# 94330_SKYPULSE_IOC_V1_3.net
KiCad netlist of a schematic drawn in Altium Designer
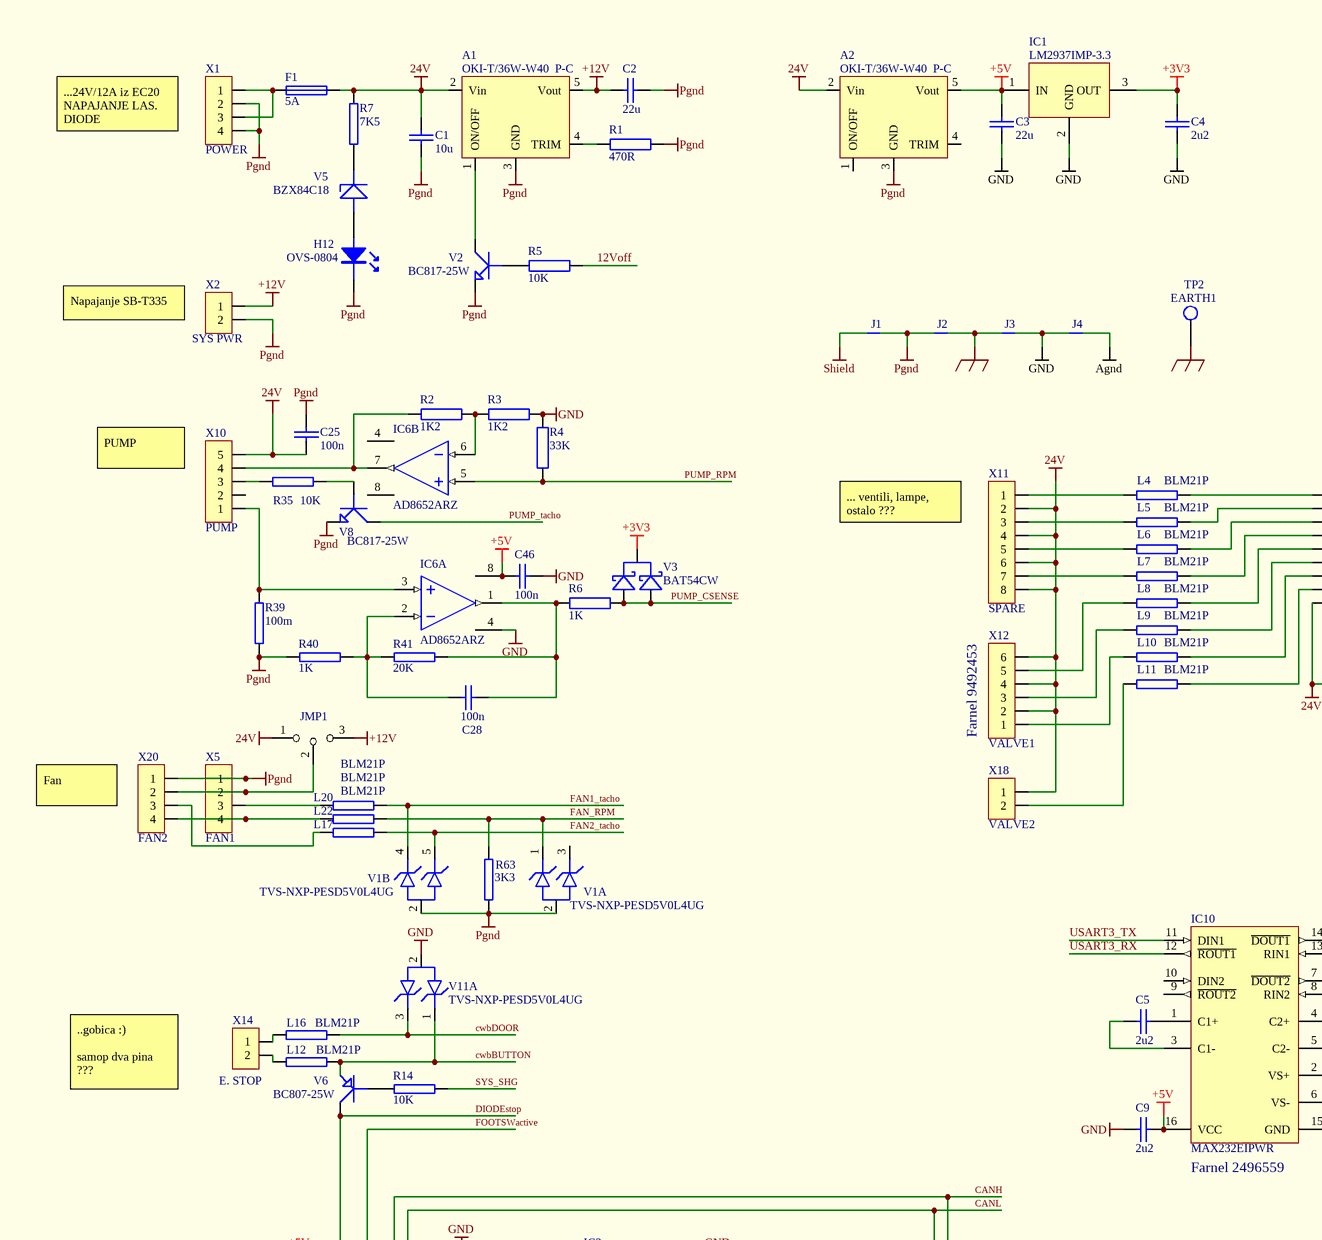
[diagram p0: 94330_SKYPULSE IOC_V1.3.SchDoc, top left]
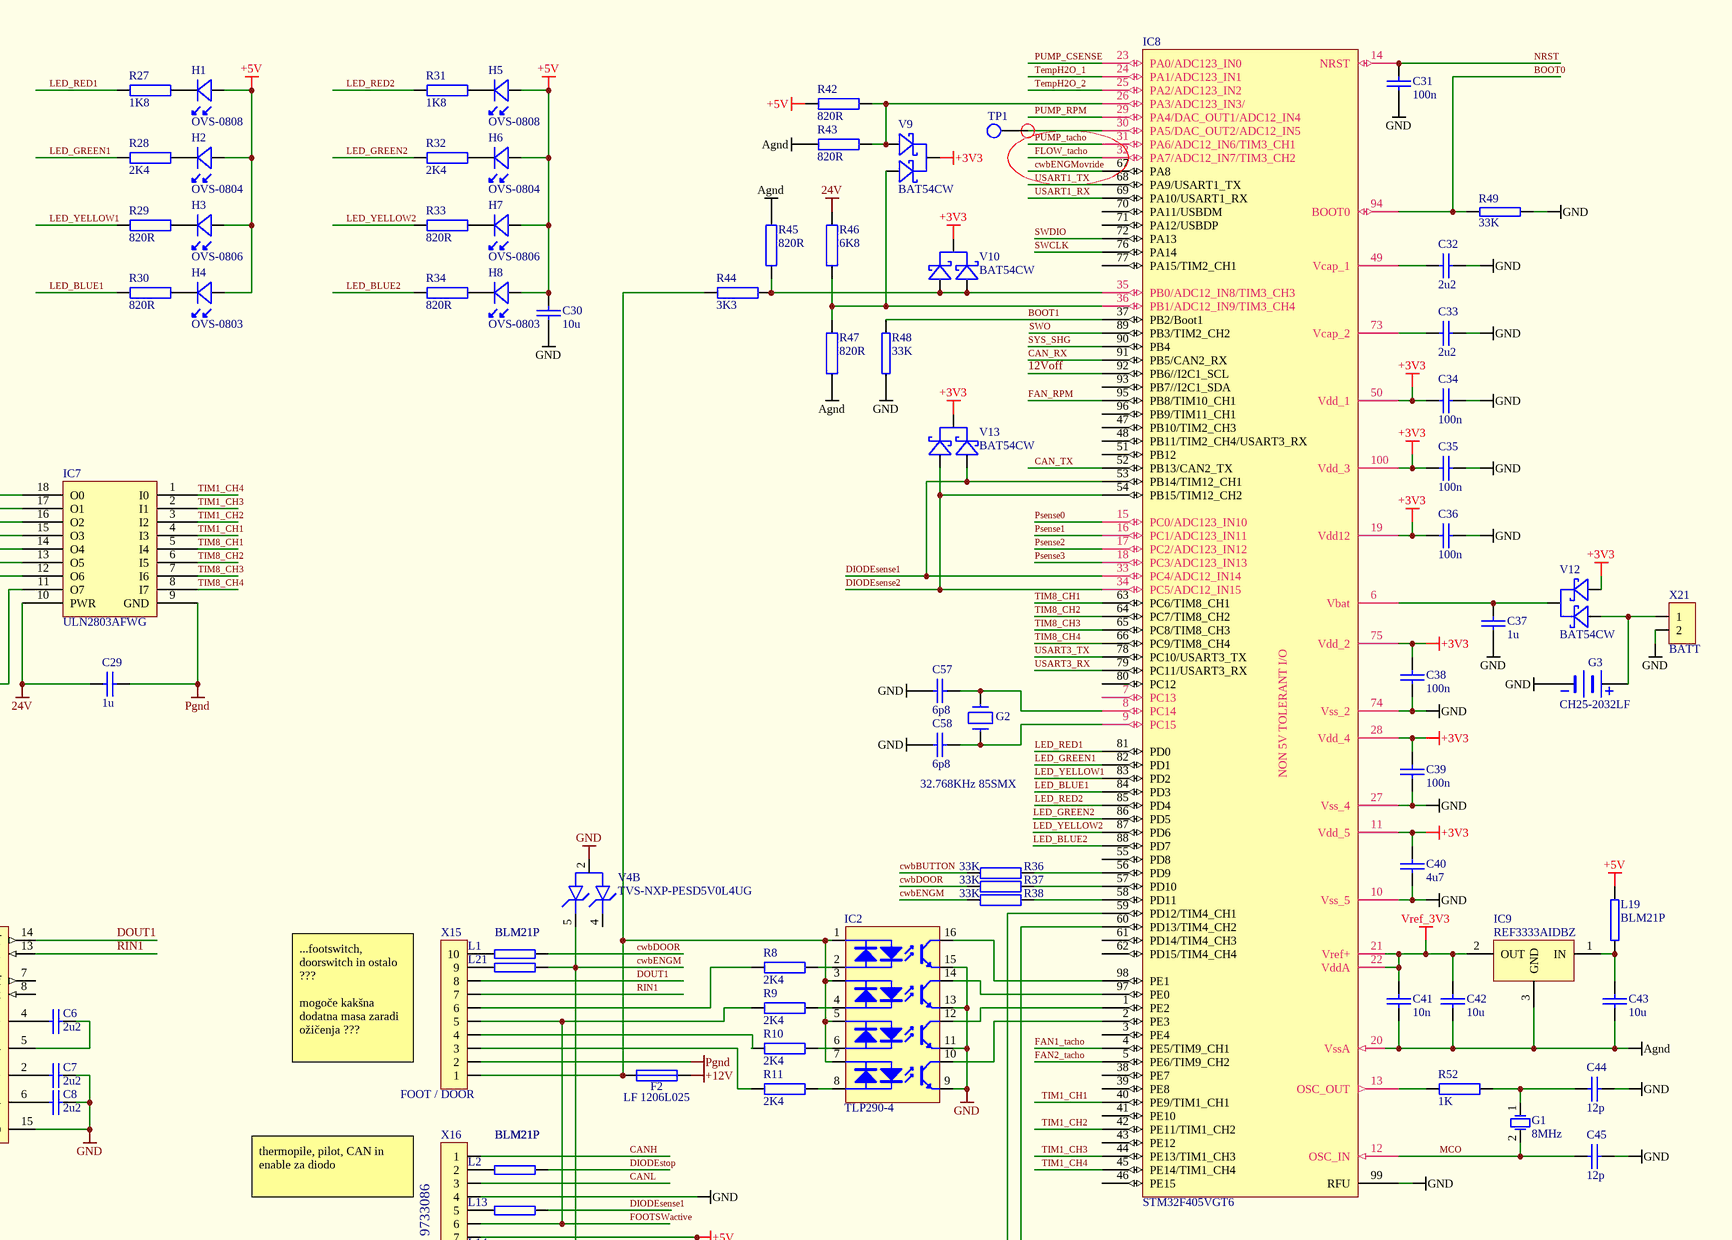
[diagram p1: 94330_SKYPULSE IOC_V1.3.SchDoc, top right]
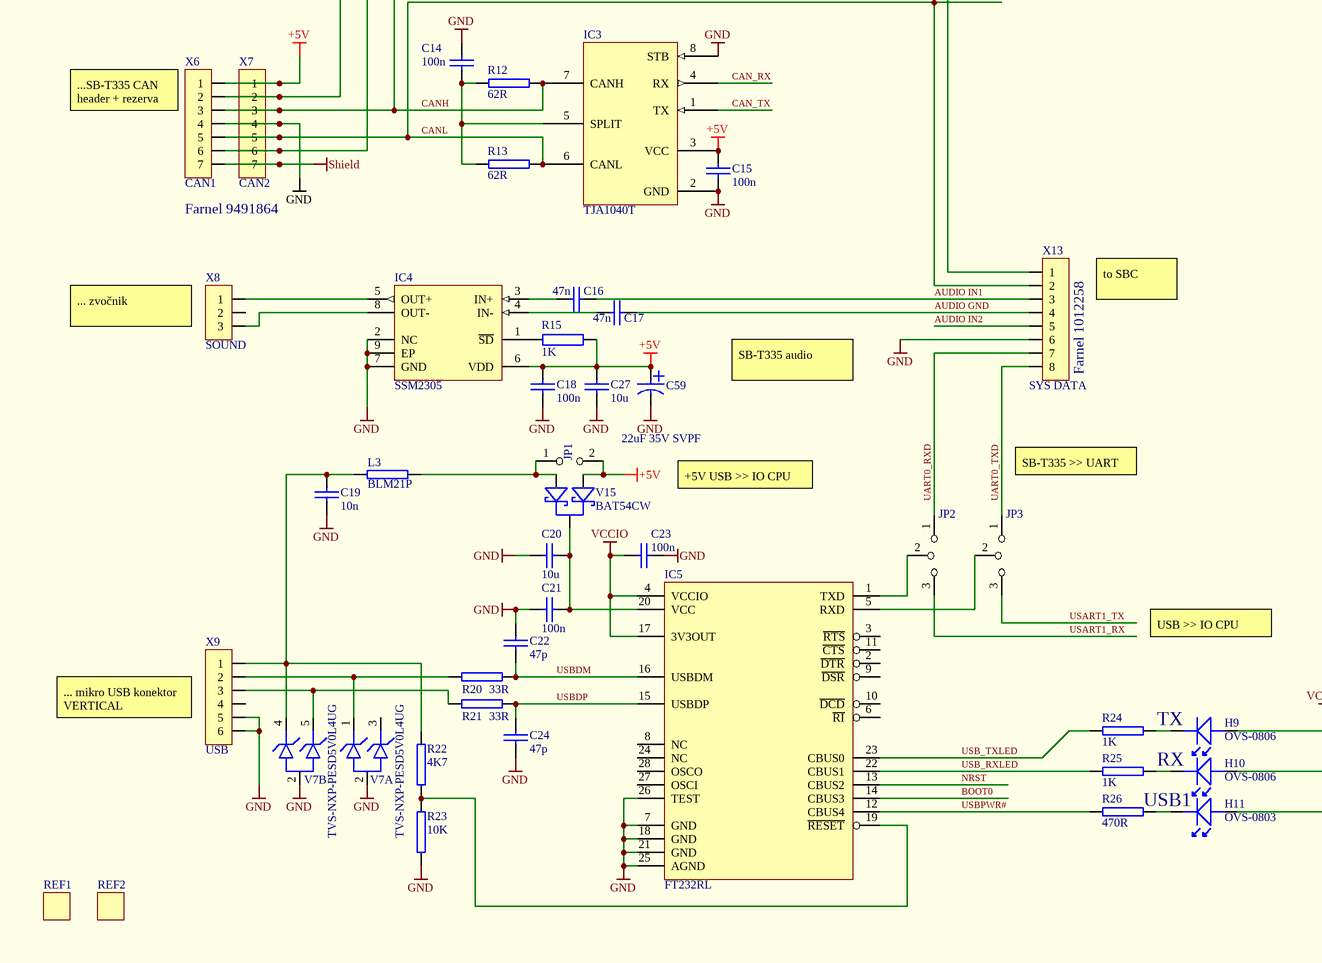
[diagram p2: 94330_SKYPULSE IOC_V1.3.SchDoc, bottom left]
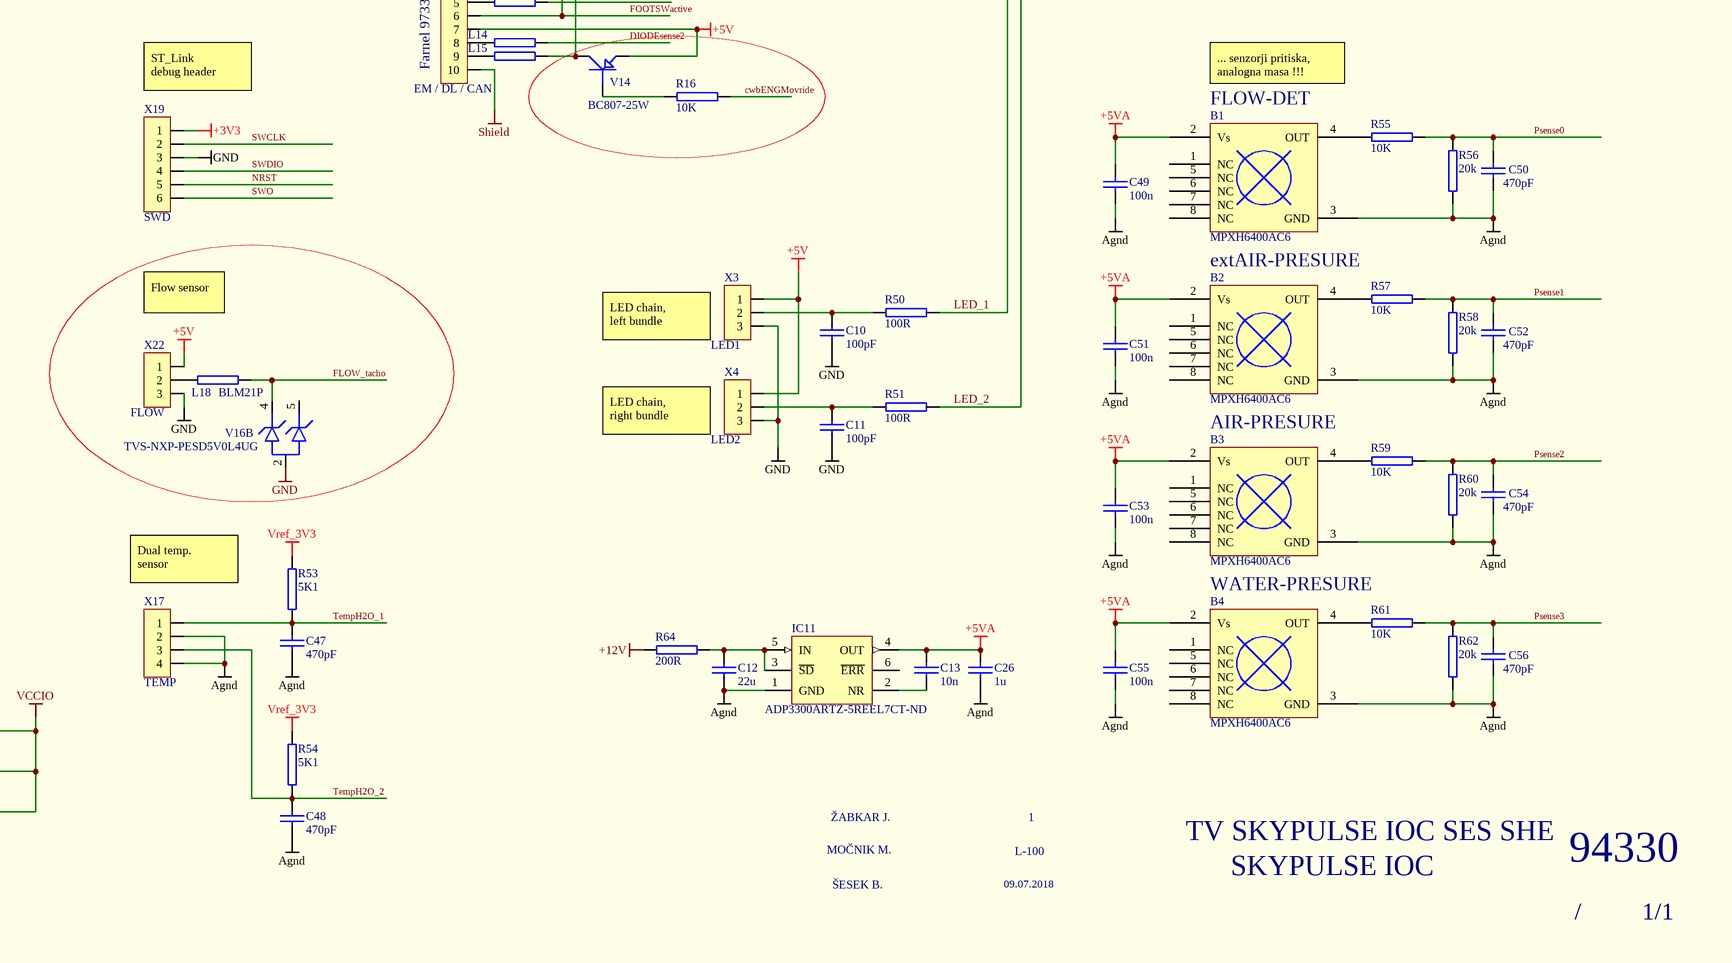
[diagram p3: 94330_SKYPULSE IOC_V1.3.SchDoc, bottom right]

(export (version "E")
  (design (tool "Eeschema 10.0.6"))
  (components
    (comp (ref "A1")
      (value "OKI-T/36W-W40  P-C")
      (footprint "DC-DC_OKI-T/36W-W40")
      (description "Selectable Output DC-DC Converter")
      (libsource (lib "Mlk-sch") (part "MURATA_OKI-T/36W-W40  X-C"))
    )
    (comp (ref "A2")
      (value "OKI-T/36W-W40  P-C")
      (footprint "DC-DC_OKI-T/36W-W40")
      (description "Selectable Output DC-DC Converter")
      (libsource (lib "Mlk-sch") (part "MURATA_OKI-T/36W-W40  X-C"))
    )
    (comp (ref "B1")
      (value "MPXH6400AC6")
      (footprint "SOIC127P1030-8N_MPXH6400AC6")
      (description "Pressure sensor, 400kPa")
      (libsource (lib "*") (part "MPXH6400A"))
    )
    (comp (ref "B2")
      (value "MPXH6400AC6")
      (footprint "SOIC127P1030-8N_MPXH6400AC6")
      (description "Pressure sensor, 400kPa")
      (libsource (lib "*") (part "MPXH6400A"))
    )
    (comp (ref "B3")
      (value "MPXH6400AC6")
      (footprint "SOIC127P1030-8N_MPXH6400AC6")
      (description "Pressure sensor, 400kPa")
      (libsource (lib "*") (part "MPXH6400A"))
    )
    (comp (ref "B4")
      (value "MPXH6400AC6")
      (footprint "SOIC127P1030-8N_MPXH6400AC6")
      (description "Pressure sensor, 400kPa")
      (libsource (lib "*") (part "MPXH6400A"))
    )
    (comp (ref "C1")
      (value "10u")
      (footprint "CAPC3225N")
      (description "KOND. 1210 10uF 50V 20% X5S")
      (libsource (lib "altium-import") (part "root_2_Cap_"))
    )
    (comp (ref "C2")
      (value "22u")
      (footprint "CAPC3225N")
      (description "KOND. 1210 22uF 25V 10% X5R")
      (libsource (lib "altium-import") (part "root_1_Cap_"))
    )
    (comp (ref "C3")
      (value "22u")
      (footprint "CAPC3225N")
      (description "KOND. 1210 22uF 25V 10% X5R")
      (libsource (lib "altium-import") (part "root_0_Cap_"))
    )
    (comp (ref "C4")
      (value "2u2")
      (footprint "0805-C-IPC-V")
      (description "KOND. 0805 2,2uF 25V 10% X7R")
      (libsource (lib "altium-import") (part "root_0_Cap_"))
    )
    (comp (ref "C5")
      (value "2u2")
      (footprint "0805-C-IPC-V")
      (description "KOND. 0805 2,2uF 25V 10% X7R")
      (libsource (lib "altium-import") (part "root_1_Cap_"))
    )
    (comp (ref "C6")
      (value "2u2")
      (footprint "0805-C-IPC-V")
      (description "KOND. 0805 2,2uF 25V 10% X7R")
      (libsource (lib "altium-import") (part "root_1_Cap_"))
    )
    (comp (ref "C7")
      (value "2u2")
      (footprint "0805-C-IPC-V")
      (description "KOND. 0805 2,2uF 25V 10% X7R")
      (libsource (lib "altium-import") (part "root_1_Cap_"))
    )
    (comp (ref "C8")
      (value "2u2")
      (footprint "0805-C-IPC-V")
      (description "KOND. 0805 2,2uF 25V 10% X7R")
      (libsource (lib "altium-import") (part "root_1_Cap_"))
    )
    (comp (ref "C9")
      (value "2u2")
      (footprint "0805-C-IPC-V")
      (description "KOND. 0805 2,2uF 25V 10% X7R")
      (libsource (lib "altium-import") (part "root_3_Cap_"))
    )
    (comp (ref "C10")
      (value "100pF")
      (footprint "0805-C-IPC-V")
      (description "KOND. 0805 100pF 50V 5% COG")
      (libsource (lib "*") (part "C"))
    )
    (comp (ref "C11")
      (value "100pF")
      (footprint "0805-C-IPC-V")
      (description "KOND. 0805 100pF 50V 5% COG")
      (libsource (lib "*") (part "C"))
    )
    (comp (ref "C12")
      (value "22u")
      (footprint "CAPC3225N")
      (description "KOND. 1210 22uF 25V 10% X5R")
      (libsource (lib "altium-import") (part "root_2_Cap_"))
    )
    (comp (ref "C13")
      (value "10n")
      (footprint "0805-C-IPC-V")
      (description "KOND. 0805 10nF 10% 50V X7R")
      (libsource (lib "Main") (part "C"))
    )
    (comp (ref "C14")
      (value "100n")
      (footprint "0805-C-IPC-V")
      (description "KOND. 0805 100nF 50V 10% X7R")
      (libsource (lib "Main") (part "C"))
    )
    (comp (ref "C15")
      (value "100n")
      (footprint "0805-C-IPC-V")
      (description "KOND. 0805 100nF 50V 10% X7R")
      (libsource (lib "Main") (part "C"))
    )
    (comp (ref "C16")
      (value "47n")
      (footprint "0805-C-IPC-V")
      (description "KOND. 0805 47nF 50V X7R 10%")
      (libsource (lib "Main") (part "C"))
    )
    (comp (ref "C17")
      (value "47n")
      (footprint "0805-C-IPC-V")
      (description "KOND. 0805 47nF 50V X7R 10%")
      (libsource (lib "Main") (part "C"))
    )
    (comp (ref "C18")
      (value "100n")
      (footprint "0805-C-IPC-V")
      (description "KOND. 0805 100nF 50V 10% X7R")
      (libsource (lib "Main") (part "C"))
    )
    (comp (ref "C19")
      (value "10n")
      (footprint "0805-C-IPC-V")
      (description "KOND. 0805 10nF 10% 50V X7R")
      (libsource (lib "*") (part "C"))
    )
    (comp (ref "C20")
      (value "10u")
      (footprint "0805-C-IPC-V")
      (description "KOND. 0805 10uF 10V 10% X7R")
      (libsource (lib "*") (part "CAP"))
    )
    (comp (ref "C21")
      (value "100n")
      (footprint "0805-C-IPC-V")
      (description "KOND. 0805 100nF 50V 10% X7R")
      (libsource (lib "*") (part "C"))
    )
    (comp (ref "C22")
      (value "47p")
      (footprint "0805-C-V")
      (description "KOND. 0805 47pF 50V 5% COG")
      (libsource (lib "*") (part "C"))
    )
    (comp (ref "C23")
      (value "100n")
      (footprint "0805-C-IPC-V")
      (description "KOND. 0805 100nF 50V 10% X7R")
      (libsource (lib "*") (part "C"))
    )
    (comp (ref "C24")
      (value "47p")
      (footprint "0805-C-V")
      (description "KOND. 0805 47pF 50V 5% COG")
      (libsource (lib "*") (part "C"))
    )
    (comp (ref "C25")
      (value "100n")
      (footprint "0805-C-IPC-V")
      (description "KOND. 0805 100nF 50V 10% X7R")
      (libsource (lib "*") (part "C"))
    )
    (comp (ref "C26")
      (value "1u")
      (footprint "0805-C-IPC-V")
      (description "KOND. 0805 1uF 50V 10% X7R")
      (libsource (lib "Main") (part "C"))
    )
    (comp (ref "C27")
      (value "10u")
      (footprint "0805-C-IPC-V")
      (description "KOND. 0805 10uF 10V 10% X7R")
      (libsource (lib "altium-import") (part "root_2_Cap_"))
    )
    (comp (ref "C28")
      (value "100n")
      (footprint "0805-C-IPC-V")
      (description "KOND. 0805 100nF 50V 10% X7R")
      (libsource (lib "Fotona") (part "Cap"))
    )
    (comp (ref "C29")
      (value "1u")
      (footprint "0805-C-IPC-V")
      (description "KOND. 0805 1uF 50V 10% X7R")
      (libsource (lib "Main") (part "C"))
    )
    (comp (ref "C30")
      (value "10u")
      (footprint "0805-C-IPC-V")
      (description "KOND. 0805 10uF 10V 10% X7R")
      (libsource (lib "Fotona") (part "Cap"))
    )
    (comp (ref "C31")
      (value "100n")
      (footprint "0805-C-IPC-V")
      (description "KOND. 0805 100nF 50V 10% X7R")
      (libsource (lib "Fotona") (part "Cap"))
    )
    (comp (ref "C32")
      (value "2u2")
      (footprint "0805-C-IPC-V")
      (description "KOND. 0805 2,2uF 25V 10% X7R")
      (libsource (lib "Fotona") (part "Cap"))
    )
    (comp (ref "C33")
      (value "2u2")
      (footprint "0805-C-IPC-V")
      (description "KOND. 0805 2,2uF 25V 10% X7R")
      (libsource (lib "Fotona") (part "Cap"))
    )
    (comp (ref "C34")
      (value "100n")
      (footprint "0805-C-IPC-V")
      (description "KOND. 0805 100nF 50V 10% X7R")
      (libsource (lib "Main") (part "C"))
    )
    (comp (ref "C35")
      (value "100n")
      (footprint "0805-C-IPC-V")
      (description "KOND. 0805 100nF 50V 10% X7R")
      (libsource (lib "Main") (part "C"))
    )
    (comp (ref "C36")
      (value "100n")
      (footprint "0805-C-IPC-V")
      (description "KOND. 0805 100nF 50V 10% X7R")
      (libsource (lib "Main") (part "C"))
    )
    (comp (ref "C37")
      (value "1u")
      (footprint "0805-C-IPC-V")
      (description "KOND. 0805 1uF 50V 10% X7R")
      (libsource (lib "Main") (part "C"))
    )
    (comp (ref "C38")
      (value "100n")
      (footprint "0805-C-IPC-V")
      (description "KOND. 0805 100nF 50V 10% X7R")
      (libsource (lib "Main") (part "C"))
    )
    (comp (ref "C39")
      (value "100n")
      (footprint "0805-C-IPC-V")
      (description "KOND. 0805 100nF 50V 10% X7R")
      (libsource (lib "Main") (part "C"))
    )
    (comp (ref "C40")
      (value "4u7")
      (footprint "0805-C-IPC-V")
      (description "KOND. 0805 4,7uF 25V 10% X5R")
      (libsource (lib "Fotona") (part "Cap"))
    )
    (comp (ref "C41")
      (value "10n")
      (footprint "0805-C-IPC-V")
      (description "KOND. 0805 10nF 10% 50V X7R")
      (libsource (lib "Fotona") (part "Cap"))
    )
    (comp (ref "C42")
      (value "10u")
      (footprint "0805-C-IPC-V")
      (description "KOND. 0805 10uF 10V 10% X7R")
      (libsource (lib "Fotona") (part "Cap"))
    )
    (comp (ref "C43")
      (value "10u")
      (footprint "0805-C-IPC-V")
      (description "KOND. 0805 10uF 10V 10% X7R")
      (libsource (lib "Fotona") (part "Cap"))
    )
    (comp (ref "C44")
      (value "12p")
      (footprint "0805-C-IPC-V")
      (description "KOND. 0805 12pF 50V 5% COG")
      (libsource (lib "Fotona") (part "Cap"))
    )
    (comp (ref "C45")
      (value "12p")
      (footprint "0805-C-IPC-V")
      (description "KOND. 0805 12pF 50V 5% COG")
      (libsource (lib "Fotona") (part "Cap"))
    )
    (comp (ref "C46")
      (value "100n")
      (footprint "0805-C-IPC-V")
      (description "KOND. 0805 100nF 50V 10% X7R")
      (libsource (lib "Fotona") (part "Cap"))
    )
    (comp (ref "C47")
      (value "470pF")
      (footprint "0805-C-IPC-V")
      (description "KOND. 0805 470P 50V 5% COG")
      (libsource (lib "*") (part "C"))
    )
    (comp (ref "C48")
      (value "470pF")
      (footprint "0805-C-IPC-V")
      (description "KOND. 0805 470P 50V 5% COG")
      (libsource (lib "*") (part "C"))
    )
    (comp (ref "C49")
      (value "100n")
      (footprint "0805-C-IPC-V")
      (description "KOND. 0805 100nF 50V 10% X7R")
      (libsource (lib "Main") (part "C"))
    )
    (comp (ref "C50")
      (value "470pF")
      (footprint "0805-C-IPC-V")
      (description "KOND. 0805 470P 50V 5% COG")
      (libsource (lib "*") (part "C"))
    )
    (comp (ref "C51")
      (value "100n")
      (footprint "0805-C-IPC-V")
      (description "KOND. 0805 100nF 50V 10% X7R")
      (libsource (lib "Main") (part "C"))
    )
    (comp (ref "C52")
      (value "470pF")
      (footprint "0805-C-IPC-V")
      (description "KOND. 0805 470P 50V 5% COG")
      (libsource (lib "*") (part "C"))
    )
    (comp (ref "C53")
      (value "100n")
      (footprint "0805-C-IPC-V")
      (description "KOND. 0805 100nF 50V 10% X7R")
      (libsource (lib "Main") (part "C"))
    )
    (comp (ref "C54")
      (value "470pF")
      (footprint "0805-C-IPC-V")
      (description "KOND. 0805 470P 50V 5% COG")
      (libsource (lib "*") (part "C"))
    )
    (comp (ref "C55")
      (value "100n")
      (footprint "0805-C-IPC-V")
      (description "KOND. 0805 100nF 50V 10% X7R")
      (libsource (lib "Main") (part "C"))
    )
    (comp (ref "C56")
      (value "470pF")
      (footprint "0805-C-IPC-V")
      (description "KOND. 0805 470P 50V 5% COG")
      (libsource (lib "*") (part "C"))
    )
    (comp (ref "C57")
      (value "6p8")
      (footprint "0805-C-IPC-V")
      (description "KOND. 0805 6,8pF 50V 5% COG")
      (libsource (lib "Fotona") (part "Cap"))
    )
    (comp (ref "C58")
      (value "6p8")
      (footprint "0805-C-IPC-V")
      (description "KOND. 0805 6,8pF 50V 5% COG")
      (libsource (lib "Fotona") (part "Cap"))
    )
    (comp (ref "C59")
      (value "22uF 35V SVPF")
      (footprint "CAPAE66W54HN")
      (description "KONDEN. ELEK. SMD 22UF 35V")
      (libsource (lib "Mlk-sch") (part "C-EL"))
    )
    (comp (ref "F1")
      (value "5A")
      (footprint "FUSE_154_ LITTELFUSE")
      (description "FUSE OMNI-BLOK Series 5 A")
      (libsource (lib "MA_DEVICE_1") (part "FUSE"))
    )
    (comp (ref "F2")
      (value "LF 1206L025")
      (footprint "FUSEC3216X09N")
      (description "PPTC Resettable Fuse")
      (libsource (lib "*") (part "FUSE1"))
    )
    (comp (ref "G1")
      (value "8MHz")
      (footprint "JXG53P2")
      (description "Crystal, 8 MHz, SMD, 5mm x 3.2mm")
      (libsource (lib "Fotona") (part "XTAL"))
    )
    (comp (ref "G2")
      (value "32.768KHz 85SMX")
      (footprint "QUARTZ-85SMX")
      (description "Crystal, 32.768 kHz, SMD")
      (libsource (lib "*") (part "CRYSTAL"))
    )
    (comp (ref "G3")
      (value "CH25-2032LF")
      (footprint "BATTERY HOLDER-20")
      (description "Li CELL 3V, 3/2 PIN, HOR/VERT POS")
      (libsource (lib "Mlk-sch") (part "BATTERY LI 3V"))
    )
    (comp (ref "H1")
      (value "OVS-0808")
      (footprint "LED_0805_RED")
      (description "LED")
      (libsource (lib "Fotona") (part "LED"))
    )
    (comp (ref "H2")
      (value "OVS-0804")
      (footprint "LED_0805_GREEN")
      (description "LED")
      (libsource (lib "Fotona") (part "LED"))
    )
    (comp (ref "H3")
      (value "OVS-0806")
      (footprint "LED_0805_YELLOW")
      (description "LED")
      (libsource (lib "Fotona") (part "LED"))
    )
    (comp (ref "H4")
      (value "OVS-0803")
      (footprint "LED_0805_BLUE")
      (description "LED")
      (libsource (lib "Fotona") (part "LED"))
    )
    (comp (ref "H5")
      (value "OVS-0808")
      (footprint "LED_0805_RED")
      (description "LED")
      (libsource (lib "Fotona") (part "LED"))
    )
    (comp (ref "H6")
      (value "OVS-0804")
      (footprint "LED_0805_GREEN")
      (description "LED")
      (libsource (lib "Fotona") (part "LED"))
    )
    (comp (ref "H7")
      (value "OVS-0806")
      (footprint "LED_0805_YELLOW")
      (description "LED")
      (libsource (lib "Fotona") (part "LED"))
    )
    (comp (ref "H8")
      (value "OVS-0803")
      (footprint "LED_0805_BLUE")
      (description "LED")
      (libsource (lib "Fotona") (part "LED"))
    )
    (comp (ref "H9")
      (value "OVS-0806")
      (footprint "LED_0805_YELLOW")
      (description "LED")
      (libsource (lib "*") (part "LED0805"))
    )
    (comp (ref "H10")
      (value "OVS-0806")
      (footprint "LED_0805_YELLOW")
      (description "LED")
      (libsource (lib "*") (part "LED0805"))
    )
    (comp (ref "H11")
      (value "OVS-0803")
      (footprint "LED_0805_BLUE")
      (description "LED")
      (libsource (lib "*") (part "LED0805"))
    )
    (comp (ref "H12")
      (value "OVS-0804")
      (footprint "LED_0805_GREEN")
      (description "LED")
      (libsource (lib "MA_DEVICE_1") (part "D_LED"))
    )
    (comp (ref "IC1")
      (value "LM2937IMP-3.3")
      (footprint "FOTONA_IPC7351_DISCRETE:SOT223-4N-V")
      (description "Fixed 3V3 Regulator")
      (libsource (lib "Fotona") (part "LM2937IMP"))
    )
    (comp (ref "IC2")
      (value "TLP290-4")
      (footprint "SOIC127P700X265-16N")
      (description "Optocoupler, Transistor Output, 4 Channel")
      (libsource (lib "Mlk-sch") (part "OPTOCOUPLER-QUAD"))
    )
    (comp (ref "IC3")
      (value "TJA1040T")
      (footprint "SO_8")
      (description "CAN Bus, Transceiver")
      (libsource (lib "*") (part "TJA1040"))
    )
    (comp (ref "IC4")
      (value "SSM2305")
      (footprint "SON50P300X85_HS-9N")
      (description "Audio Power Amplifier")
      (libsource (lib "Mlk-sch") (part "SSM2305"))
    )
    (comp (ref "IC5")
      (value "FT232RL")
      (footprint "SOP65P780-28N")
      (description "USB to Serial port converter")
      (libsource (lib "*") (part "FT232RL"))
    )
    (comp (ref "IC6")
      (value "AD8652ARZ")
      (footprint "SOIC127P600-8N")
      (description "Dual CMOS RR Op Amp")
      (libsource (lib "Fotona") (part "OPAMP_DUAL"))
    )
    (comp (ref "IC7")
      (value "ULN2803AFWG")
      (footprint "SOIC127P1030-18N")
      (description "Bipolar Transistor Array, Darlington, NPN")
      (libsource (lib "*") (part "ULN2804"))
    )
    (comp (ref "IC8")
      (value "STM32F405VGT6")
      (footprint "LQFP100_N")
      (description "STM32 ARM-based 32-bit MCU")
      (libsource (lib "Fotona") (part "STM32F205VGT6"))
    )
    (comp (ref "IC9")
      (value "REF3333AIDBZ")
      (footprint "FOTONA_IPC7351_DISCRETE:SOT23-3N")
      (description "3V3 Voltage Reference")
      (libsource (lib "Fotona") (part "REF33XX"))
    )
    (comp (ref "IC10")
      (value "MAX232EIPWR")
      (footprint "FOTONA_IPC7351_SO:TSOP65P640-16N")
      (description "Dual RS-232 Driver / Receiver")
      (libsource (lib "altium-import") (part "root_0_CMP-0299-00572-2_"))
    )
    (comp (ref "IC11")
      (value "ADP3300ARTZ-5REEL7CT-ND")
      (footprint "SOT23-6N")
      (description "LDO Voltage Regulator")
      (libsource (lib "Mlk-sch") (part "ADP3300"))
    )
    (comp (ref "J1") (value "JMP-GND") (footprint "JMP-GND") (libsource (lib "Mlk-sch") (part "JMP-GND")))
    (comp (ref "J2") (value "JMP-GND") (footprint "JMP-GND") (libsource (lib "Mlk-sch") (part "JMP-GND")))
    (comp (ref "J3") (value "JMP-GND") (footprint "JMP-GND") (libsource (lib "Mlk-sch") (part "JMP-GND")))
    (comp (ref "J4") (value "JMP-GND") (footprint "JMP-GND") (libsource (lib "Mlk-sch") (part "JMP-GND")))
    (comp (ref "JMP1") (value "~") (description "JUMPER") (libsource (lib "MA_DEVICE_1") (part "JMP3")))
    (comp (ref "JP1")
      (value "~")
      (footprint "SIP_2")
      (description "Kontaktna letev 2pina")
      (libsource (lib "MA_DEVICE_1") (part "JMP2"))
    )
    (comp (ref "JP2")
      (value "~")
      (footprint "JMP3-SMD-1,2,3")
      (description "Kontaktna letev 3 pin")
      (libsource (lib "MA_DEVICE_1") (part "JMP3"))
    )
    (comp (ref "JP3")
      (value "~")
      (footprint "JMP3-SMD-1,2,3")
      (description "Kontaktna letev 3 pin")
      (libsource (lib "MA_DEVICE_1") (part "JMP3"))
    )
    (comp (ref "L1")
      (value "BLM21P")
      (footprint "INDC2012N")
      (description "Ferrite Bead, 0805")
      (libsource (lib "*") (part "BLM21"))
    )
    (comp (ref "L2")
      (value "BLM21P")
      (footprint "INDC2012N")
      (description "Ferrite Bead, 0805")
      (libsource (lib "*") (part "BLM21"))
    )
    (comp (ref "L3")
      (value "BLM21P")
      (footprint "INDC2012N")
      (description "Ferrite Bead, 0805")
      (libsource (lib "*") (part "BLM21"))
    )
    (comp (ref "L4")
      (value "BLM21P")
      (footprint "INDC2012N")
      (description "Ferrite Bead, 0805")
      (libsource (lib "*") (part "BLM21"))
    )
    (comp (ref "L5")
      (value "BLM21P")
      (footprint "INDC2012N")
      (description "Ferrite Bead, 0805")
      (libsource (lib "*") (part "BLM21"))
    )
    (comp (ref "L6")
      (value "BLM21P")
      (footprint "INDC2012N")
      (description "Ferrite Bead, 0805")
      (libsource (lib "*") (part "BLM21"))
    )
    (comp (ref "L7")
      (value "BLM21P")
      (footprint "INDC2012N")
      (description "Ferrite Bead, 0805")
      (libsource (lib "*") (part "BLM21"))
    )
    (comp (ref "L8")
      (value "BLM21P")
      (footprint "INDC2012N")
      (description "Ferrite Bead, 0805")
      (libsource (lib "*") (part "BLM21"))
    )
    (comp (ref "L9")
      (value "BLM21P")
      (footprint "INDC2012N")
      (description "Ferrite Bead, 0805")
      (libsource (lib "*") (part "BLM21"))
    )
    (comp (ref "L10")
      (value "BLM21P")
      (footprint "INDC2012N")
      (description "Ferrite Bead, 0805")
      (libsource (lib "*") (part "BLM21"))
    )
    (comp (ref "L11")
      (value "BLM21P")
      (footprint "INDC2012N")
      (description "Ferrite Bead, 0805")
      (libsource (lib "*") (part "BLM21"))
    )
    (comp (ref "L12")
      (value "BLM21P")
      (footprint "INDC2012N")
      (description "Ferrite Bead, 0805")
      (libsource (lib "*") (part "BLM21"))
    )
    (comp (ref "L13")
      (value "BLM21P")
      (footprint "INDC2012N")
      (description "Ferrite Bead, 0805")
      (libsource (lib "*") (part "BLM21"))
    )
    (comp (ref "L14")
      (value "BLM21P")
      (footprint "INDC2012N")
      (description "Ferrite Bead, 0805")
      (libsource (lib "*") (part "BLM21"))
    )
    (comp (ref "L15")
      (value "BLM21P")
      (footprint "INDC2012N")
      (description "Ferrite Bead, 0805")
      (libsource (lib "*") (part "BLM21"))
    )
    (comp (ref "L16")
      (value "BLM21P")
      (footprint "INDC2012N")
      (description "Ferrite Bead, 0805")
      (libsource (lib "*") (part "BLM21"))
    )
    (comp (ref "L17")
      (value "BLM21P")
      (footprint "INDC2012N")
      (description "Ferrite Bead, 0805")
      (libsource (lib "*") (part "BLM21"))
    )
    (comp (ref "L18")
      (value "BLM21P")
      (footprint "INDC2012N")
      (description "Ferrite Bead, 0805")
      (libsource (lib "*") (part "BLM21"))
    )
    (comp (ref "L19")
      (value "BLM21P")
      (footprint "INDC2012N")
      (description "Ferrite Bead, 0805")
      (libsource (lib "*") (part "BLM21"))
    )
    (comp (ref "L20")
      (value "BLM21P")
      (footprint "INDC2012N")
      (description "Ferrite Bead, 0805")
      (libsource (lib "*") (part "BLM21"))
    )
    (comp (ref "L21")
      (value "BLM21P")
      (footprint "INDC2012N")
      (description "Ferrite Bead, 0805")
      (libsource (lib "*") (part "BLM21"))
    )
    (comp (ref "L22")
      (value "BLM21P")
      (footprint "INDC2012N")
      (description "Ferrite Bead, 0805")
      (libsource (lib "*") (part "BLM21"))
    )
    (comp (ref "R1")
      (value "470R")
      (footprint "0805-R-IPC-V")
      (description "UPOR 0805 470R 1% 0,125W")
      (libsource (lib "Fotona") (part "Res"))
    )
    (comp (ref "R2")
      (value "1K2")
      (footprint "0805-R-IPC-V")
      (description "UPOR 0805 1,2K 1% 0,125W")
      (libsource (lib "Fotona") (part "Res"))
    )
    (comp (ref "R3")
      (value "1K2")
      (footprint "0805-R-IPC-V")
      (description "UPOR 0805 1,2K 1% 0,125W")
      (libsource (lib "Fotona") (part "Res"))
    )
    (comp (ref "R4")
      (value "33K")
      (footprint "0805-R-V")
      (description "UPOR 0805 33K 1% 0,125W")
      (libsource (lib "Fotona") (part "Res"))
    )
    (comp (ref "R5")
      (value "10K")
      (footprint "0805-R-IPC-V")
      (description "UPOR 0805 10K 1% 0,125W")
      (libsource (lib "Fotona") (part "Res"))
    )
    (comp (ref "R6")
      (value "1K")
      (footprint "0805-R-IPC-V")
      (description "UPOR 0805 1K 1% 0,125W")
      (libsource (lib "Fotona") (part "Res"))
    )
    (comp (ref "R7")
      (value "7K5")
      (footprint "0805-R-IPC-V")
      (description "UPOR 0805 7,5K 1% 0,125W")
      (libsource (lib "*") (part "R"))
    )
    (comp (ref "R8")
      (value "2K4")
      (footprint "0805-R-IPC-V")
      (description "UPOR 0805 2,4K 1% 0,125W")
      (libsource (lib "Fotona") (part "Res"))
    )
    (comp (ref "R9")
      (value "2K4")
      (footprint "0805-R-IPC-V")
      (description "UPOR 0805 2,4K 1% 0,125W")
      (libsource (lib "Fotona") (part "Res"))
    )
    (comp (ref "R10")
      (value "2K4")
      (footprint "0805-R-IPC-V")
      (description "UPOR 0805 2,4K 1% 0,125W")
      (libsource (lib "Fotona") (part "Res"))
    )
    (comp (ref "R11")
      (value "2K4")
      (footprint "0805-R-IPC-V")
      (description "UPOR 0805 2,4K 1% 0,125W")
      (libsource (lib "Fotona") (part "Res"))
    )
    (comp (ref "R12")
      (value "62R")
      (footprint "0805-R-IPC-V")
      (description "UPOR 0805 62R 1% 0,125W")
      (libsource (lib "Main") (part "R"))
    )
    (comp (ref "R13")
      (value "62R")
      (footprint "0805-R-IPC-V")
      (description "UPOR 0805 62R 1% 0,125W")
      (libsource (lib "Main") (part "R"))
    )
    (comp (ref "R14")
      (value "10K")
      (footprint "0805-R-IPC-V")
      (description "UPOR 0805 10K 1% 0,125W")
      (libsource (lib "Main") (part "R"))
    )
    (comp (ref "R15")
      (value "1K")
      (footprint "0805-R-IPC-V")
      (description "UPOR 0805 1K 1% 0,125W")
      (libsource (lib "Fotona") (part "Res"))
    )
    (comp (ref "R16")
      (value "10K")
      (footprint "0805-R-IPC-V")
      (description "UPOR 0805 10K 1% 0,125W")
      (libsource (lib "Main") (part "R"))
    )
    (comp (ref "R20")
      (value "33R")
      (footprint "0805-R-IPC-V")
      (description "UPOR 0805 33R 1% 0,125W")
      (libsource (lib "*") (part "R"))
    )
    (comp (ref "R21")
      (value "33R")
      (footprint "0805-R-IPC-V")
      (description "UPOR 0805 33R 1% 0,125W")
      (libsource (lib "*") (part "R"))
    )
    (comp (ref "R22")
      (value "4K7")
      (footprint "0805-R-IPC-V")
      (description "UPOR 0805 4,7K 1% 0,125W")
      (libsource (lib "*") (part "R"))
    )
    (comp (ref "R23")
      (value "10K")
      (footprint "0805-R-IPC-V")
      (description "UPOR 0805 10K 1% 0,125W")
      (libsource (lib "*") (part "R"))
    )
    (comp (ref "R24")
      (value "1K")
      (footprint "0805-R-IPC-V")
      (description "UPOR 0805 1K 1% 0,125W")
      (libsource (lib "*") (part "R"))
    )
    (comp (ref "R25")
      (value "1K")
      (footprint "0805-R-IPC-V")
      (description "UPOR 0805 1K 1% 0,125W")
      (libsource (lib "*") (part "R"))
    )
    (comp (ref "R26")
      (value "470R")
      (footprint "0805-R-IPC-V")
      (description "UPOR 0805 470R 1% 0,125W")
      (libsource (lib "*") (part "R"))
    )
    (comp (ref "R27")
      (value "1K8")
      (footprint "0805-R-IPC-V")
      (description "UPOR 0805 1,8K 1% 0,125W")
      (libsource (lib "Fotona") (part "Res"))
    )
    (comp (ref "R28")
      (value "2K4")
      (footprint "0805-R-IPC-V")
      (description "UPOR 0805 2,4K 1% 0,125W")
      (libsource (lib "Fotona") (part "Res"))
    )
    (comp (ref "R29")
      (value "820R")
      (footprint "0805-R-IPC-V")
      (description "UPOR 0805 820R 1% 0,125W")
      (libsource (lib "Fotona") (part "Res"))
    )
    (comp (ref "R30")
      (value "820R")
      (footprint "0805-R-IPC-V")
      (description "UPOR 0805 820R 1% 0,125W")
      (libsource (lib "Fotona") (part "Res"))
    )
    (comp (ref "R31")
      (value "1K8")
      (footprint "0805-R-IPC-V")
      (description "UPOR 0805 1,8K 1% 0,125W")
      (libsource (lib "Fotona") (part "Res"))
    )
    (comp (ref "R32")
      (value "2K4")
      (footprint "0805-R-IPC-V")
      (description "UPOR 0805 2,4K 1% 0,125W")
      (libsource (lib "Fotona") (part "Res"))
    )
    (comp (ref "R33")
      (value "820R")
      (footprint "0805-R-IPC-V")
      (description "UPOR 0805 820R 1% 0,125W")
      (libsource (lib "Fotona") (part "Res"))
    )
    (comp (ref "R34")
      (value "820R")
      (footprint "0805-R-IPC-V")
      (description "UPOR 0805 820R 1% 0,125W")
      (libsource (lib "Fotona") (part "Res"))
    )
    (comp (ref "R35")
      (value "10K")
      (footprint "0805-R-IPC-V")
      (description "UPOR 0805 10K 1% 0,125W")
      (libsource (lib "Main") (part "R"))
    )
    (comp (ref "R36")
      (value "33K")
      (footprint "0805-R-IPC-V")
      (description "UPOR 0805 33K 1% 0,125W")
      (fields (field (name "TOLERANCE") "1%") (field (name "POWER") "0.063W"))
      (libsource (lib "Fotona") (part "Res"))
    )
    (comp (ref "R37")
      (value "33K")
      (footprint "0805-R-IPC-V")
      (description "UPOR 0805 33K 1% 0,125W")
      (fields (field (name "TOLERANCE") "1%") (field (name "POWER") "0.063W"))
      (libsource (lib "Fotona") (part "Res"))
    )
    (comp (ref "R38")
      (value "33K")
      (footprint "0805-R-IPC-V")
      (description "UPOR 0805 33K 1% 0,125W")
      (fields (field (name "TOLERANCE") "1%") (field (name "POWER") "0.063W"))
      (libsource (lib "Fotona") (part "Res"))
    )
    (comp (ref "R39")
      (value "100m")
      (footprint "RESC3216N")
      (description "SMD Current Sense Resistor")
      (libsource (lib "Main") (part "R"))
    )
    (comp (ref "R40")
      (value "1K")
      (footprint "0805-R-IPC-V")
      (description "UPOR 0805 1K 1% 0,125W")
      (libsource (lib "Main") (part "R"))
    )
    (comp (ref "R41")
      (value "20K")
      (footprint "0805-R-IPC-V")
      (description "UPOR 0805 20K 1% 0,125W")
      (libsource (lib "Main") (part "R"))
    )
    (comp (ref "R42")
      (value "820R")
      (footprint "0805-R-IPC-V")
      (description "UPOR 0805 820R 1% 0,125W")
      (libsource (lib "Fotona") (part "Res"))
    )
    (comp (ref "R43")
      (value "820R")
      (footprint "0805-R-IPC-V")
      (description "UPOR 0805 820R 1% 0,125W")
      (libsource (lib "Fotona") (part "Res"))
    )
    (comp (ref "R44")
      (value "3K3")
      (footprint "0805-R-IPC-V")
      (description "UPOR 0805 3,3K 1% 0,125W")
      (libsource (lib "Fotona") (part "Res"))
    )
    (comp (ref "R45")
      (value "820R")
      (footprint "0805-R-IPC-V")
      (description "UPOR 0805 820R 1% 0,125W")
      (libsource (lib "Fotona") (part "Res"))
    )
    (comp (ref "R46")
      (value "6K8")
      (footprint "0805-R-IPC-V")
      (description "UPOR 0805 6,8K 1% 0,125W")
      (libsource (lib "Fotona") (part "Res"))
    )
    (comp (ref "R47")
      (value "820R")
      (footprint "0805-R-IPC-V")
      (description "UPOR 0805 820R 1% 0,125W")
      (libsource (lib "Fotona") (part "Res"))
    )
    (comp (ref "R48")
      (value "33K")
      (footprint "0805-R-IPC-V")
      (description "UPOR 0805 33K 1% 0,125W")
      (libsource (lib "Main") (part "R"))
    )
    (comp (ref "R49")
      (value "33K")
      (footprint "0805-R-IPC-V")
      (description "UPOR 0805 33K 1% 0,125W")
      (libsource (lib "Main") (part "R"))
    )
    (comp (ref "R50")
      (value "100R")
      (footprint "0805-R-IPC-V")
      (description "UPOR 0805 100R 1% 0,125W")
      (libsource (lib "Main") (part "R"))
    )
    (comp (ref "R51")
      (value "100R")
      (footprint "0805-R-IPC-V")
      (description "UPOR 0805 100R 1% 0,125W")
      (libsource (lib "Main") (part "R"))
    )
    (comp (ref "R52")
      (value "1K")
      (footprint "0805-R-IPC-V")
      (description "UPOR 0805 1K 1% 0,125W")
      (libsource (lib "Fotona") (part "Res"))
    )
    (comp (ref "R53")
      (value "5K1")
      (footprint "0805-R-IPC-V")
      (description "UPOR 0805 5,1K 1% 0,125W")
      (libsource (lib "Main") (part "R"))
    )
    (comp (ref "R54")
      (value "5K1")
      (footprint "0805-R-IPC-V")
      (description "UPOR 0805 5,1K 1% 0,125W")
      (libsource (lib "Main") (part "R"))
    )
    (comp (ref "R55")
      (value "10K")
      (footprint "0805-R-IPC-V")
      (description "UPOR 0805 10K 1% 0,125W")
      (libsource (lib "Main") (part "R"))
    )
    (comp (ref "R56")
      (value "20k")
      (footprint "0805-R-IPC-V")
      (description "UPOR 0805 20K 1% 0,125W")
      (libsource (lib "Main") (part "R"))
    )
    (comp (ref "R57")
      (value "10K")
      (footprint "0805-R-IPC-V")
      (description "UPOR 0805 10K 1% 0,125W")
      (libsource (lib "Main") (part "R"))
    )
    (comp (ref "R58")
      (value "20k")
      (footprint "0805-R-IPC-V")
      (description "UPOR 0805 20K 1% 0,125W")
      (libsource (lib "Main") (part "R"))
    )
    (comp (ref "R59")
      (value "10K")
      (footprint "0805-R-IPC-V")
      (description "UPOR 0805 10K 1% 0,125W")
      (libsource (lib "Main") (part "R"))
    )
    (comp (ref "R60")
      (value "20k")
      (footprint "0805-R-IPC-V")
      (description "UPOR 0805 20K 1% 0,125W")
      (libsource (lib "Main") (part "R"))
    )
    (comp (ref "R61")
      (value "10K")
      (footprint "0805-R-IPC-V")
      (description "UPOR 0805 10K 1% 0,125W")
      (libsource (lib "Main") (part "R"))
    )
    (comp (ref "R62")
      (value "20k")
      (footprint "0805-R-IPC-V")
      (description "UPOR 0805 20K 1% 0,125W")
      (libsource (lib "Main") (part "R"))
    )
    (comp (ref "R63")
      (value "3K3")
      (footprint "0805-R-IPC-V")
      (description "UPOR 0805 3,3K 1% 0,125W")
      (libsource (lib "Main") (part "R"))
    )
    (comp (ref "R64")
      (value "200R")
      (footprint "RESC3216N")
      (description "UPOR 1206 200R 1% 250mW")
      (libsource (lib "Main") (part "R"))
    )
    (comp (ref "REF1")
      (value "MEHAN_PART_1")
      (footprint "TP_REF")
      (libsource (lib "Altium_Device_AM_1") (part "MEHAN_PART_1"))
    )
    (comp (ref "REF2")
      (value "~")
      (footprint "TP_REF")
      (libsource (lib "Altium_Device_AM_1") (part "MEHAN_PART_1"))
    )
    (comp (ref "TP1") (value "~") (footprint "TP-09SQ") (libsource (lib "*") (part "TP")))
    (comp (ref "TP2") (value "EARTH1") (footprint "PAD") (libsource (lib "*") (part "TP")))
    (comp (ref "V1")
      (value "TVS-NXP-PESD5V0L4UG")
      (footprint "SC70-5")
      (description "TVS, NXP, PESD3V3L4UG, SOT665")
      (libsource (lib "*") (part "TVS-NXP-PESD3V3L4UG"))
    )
    (comp (ref "V2")
      (value "BC817-25W")
      (footprint "SOT323-3N-CBE")
      (description "NPN Bipolar Transistor")
      (libsource (lib "Fotona") (part "TRANSISTOR_NPN"))
    )
    (comp (ref "V3")
      (value "BAT54CW")
      (footprint "FOTONA_IPC7351_DISCRETE:SOT323-3N")
      (description "Diode Schottky Common Chatode")
      (libsource (lib "Fotona") (part "D_SCH_CK_1A1-2A2-3K"))
    )
    (comp (ref "V4")
      (value "TVS-NXP-PESD5V0L4UG")
      (footprint "SC70-5")
      (description "TVS, NXP, PESD3V3L4UG, SOT665")
      (libsource (lib "*") (part "TVS-NXP-PESD3V3L4UG"))
    )
    (comp (ref "V5")
      (value "BZX84C18")
      (footprint "SOT_23/D1")
      (description "Zener Diode SOT23")
      (libsource (lib "*") (part "ZD"))
    )
    (comp (ref "V6")
      (value "BC807-25W")
      (footprint "SOT323-3N-CBE")
      (description "PNP Bipolar Transistor")
      (libsource (lib "Fotona") (part "TRANSISTOR_PNP_1B_2E_3C"))
    )
    (comp (ref "V7")
      (value "TVS-NXP-PESD5V0L4UG")
      (footprint "SC70-5")
      (description "TVS, NXP, PESD3V3L4UG, SOT665")
      (libsource (lib "*") (part "TVS-NXP-PESD3V3L4UG"))
    )
    (comp (ref "V8")
      (value "BC817-25W")
      (footprint "SOT323-3N-CBE")
      (description "NPN Bipolar Transistor")
      (libsource (lib "Fotona") (part "TRANSISTOR_NPN"))
    )
    (comp (ref "V9")
      (value "BAT54CW")
      (footprint "FOTONA_IPC7351_DISCRETE:SOT323-3N")
      (description "Diode Schottky Common Chatode")
      (libsource (lib "Fotona") (part "D_SCH_CK_1A1-2A2-3K"))
    )
    (comp (ref "V10")
      (value "BAT54CW")
      (footprint "FOTONA_IPC7351_DISCRETE:SOT323-3N")
      (description "Diode Schottky Common Chatode")
      (libsource (lib "Fotona") (part "D_SCH_CK_1A1-2A2-3K"))
    )
    (comp (ref "V11")
      (value "TVS-NXP-PESD5V0L4UG")
      (footprint "SC70-5")
      (description "TVS, NXP, PESD3V3L4UG, SOT665")
      (libsource (lib "*") (part "TVS-NXP-PESD3V3L4UG"))
    )
    (comp (ref "V12")
      (value "BAT54CW")
      (footprint "FOTONA_IPC7351_DISCRETE:SOT323-3N")
      (description "Diode Schottky Common Chatode")
      (libsource (lib "Fotona") (part "D_SCH_CK_1A1-2A2-3K"))
    )
    (comp (ref "V13")
      (value "BAT54CW")
      (footprint "FOTONA_IPC7351_DISCRETE:SOT323-3N")
      (description "Diode Schottky Common Chatode")
      (libsource (lib "Fotona") (part "D_SCH_CK_1A1-2A2-3K"))
    )
    (comp (ref "V14")
      (value "BC807-25W")
      (footprint "SOT323-3N-CBE")
      (description "PNP Bipolar Transistor")
      (libsource (lib "Fotona") (part "TRANSISTOR_PNP_1B_2E_3C"))
    )
    (comp (ref "V15")
      (value "BAT54CW")
      (footprint "FOTONA_IPC7351_DISCRETE:SOT323-3N")
      (description "Diode Schottky Common Chatode")
      (libsource (lib "Fotona") (part "D_SCH_CK_1A1-2A2-3K"))
    )
    (comp (ref "V16")
      (value "TVS-NXP-PESD5V0L4UG")
      (footprint "SC70-5")
      (description "TVS, NXP, PESD3V3L4UG, SOT665")
      (libsource (lib "*") (part "TVS-NXP-PESD3V3L4UG"))
    )
    (comp (ref "X1")
      (value "POWER")
      (footprint "CON_4.2_4X_V")
      (description "Connector, 4.2 mm, 4 Contacts")
      (libsource (lib "MA_CONNECT_1") (part "CON 4"))
    )
    (comp (ref "X2")
      (value "SYS PWR")
      (footprint "CON_3.0_2X_V_DUAL ROW")
      (description "Connector, 3 mm, 2 Contacts")
      (libsource (lib "Fotona") (part "CON2"))
    )
    (comp (ref "X3")
      (value "LED1")
      (footprint "CON-PH_3PIN_JST")
      (description "Connector, 2 mm, 3 Contacts")
      (libsource (lib "Device") (part "CON3"))
    )
    (comp (ref "X4")
      (value "LED2")
      (footprint "CON-PH_3PIN_JST")
      (description "Connector, 2 mm, 3 Contacts")
      (libsource (lib "Device") (part "CON3"))
    )
    (comp (ref "X5")
      (value "FAN1")
      (footprint "MOLEX_47053-1000")
      (description "Connector, 2.54 mm, 4 Contacts")
      (libsource (lib "MA_CONNECT_1") (part "CON 4"))
    )
    (comp (ref "X6")
      (value "CAN1")
      (footprint "CON-PH_7PIN_JST")
      (description "Connector, 2 mm, 7 Contacts")
      (libsource (lib "Mlk-sch") (part "CON7"))
    )
    (comp (ref "X7")
      (value "CAN2")
      (footprint "CON-PH_7PIN_JST")
      (description "Connector, 2 mm, 7 Contacts")
      (libsource (lib "Mlk-sch") (part "CON7"))
    )
    (comp (ref "X8")
      (value "SOUND")
      (footprint "CON-MOLEX-53047-0310")
      (description "Connector, 1.25 mm, 3 Contacts")
      (libsource (lib "Device") (part "CON3"))
    )
    (comp (ref "X9")
      (value "USB")
      (footprint "CON_uUSB_TOP")
      (description "Connector, Micro USB Type B")
      (libsource (lib "Fotona") (part "CON6"))
    )
    (comp (ref "X10")
      (value "PUMP")
      (footprint "CON-PH_5PIN_JST")
      (description "Connector, 2 mm, 5 Contacts")
      (libsource (lib "MA_CONNECT_1") (part "CON 5"))
    )
    (comp (ref "X11")
      (value "SPARE")
      (footprint "CON-PH_8PIN_JST")
      (description "Connector, 2 mm, 8 Contacts")
      (libsource (lib "MA_CONNECT_1") (part "CON 8"))
    )
    (comp (ref "X12")
      (value "VALVE1")
      (footprint "CON-PH_6PIN_JST")
      (description "Connector, 2 mm, 6 Contacts")
      (libsource (lib "MA_CONNECT_1") (part "CON 6"))
    )
    (comp (ref "X13")
      (value "SYS DATA")
      (footprint "CON-MOLEX-53047-0810")
      (description "Connector, 1.25 mm, 8 Contacts")
      (libsource (lib "") (part "CON 8_1"))
    )
    (comp (ref "X14")
      (value "E. STOP")
      (footprint "CON-PH_2PIN_JST")
      (description "Connector, 2 mm, 2 Contacts")
      (libsource (lib "Fotona") (part "CON2"))
    )
    (comp (ref "X15")
      (value "FOOT / DOOR")
      (footprint "CON-PH_10PIN_JST")
      (description "Connector, 2 mm, 10 Contacts")
      (libsource (lib "") (part "CON 10_1"))
    )
    (comp (ref "X16")
      (value "EM / DL / CAN")
      (footprint "CON-MOLEX-53047-1010")
      (description "Connector, 1.25 mm, 10 Contacts")
      (libsource (lib "MA_CONNECT_1") (part "CON 10"))
    )
    (comp (ref "X17")
      (value "TEMP")
      (footprint "CON-PH_4PIN_JST")
      (description "Connector, 2 mm, 4 Contacts")
      (libsource (lib "MA_CONNECT_1") (part "CON 4"))
    )
    (comp (ref "X18")
      (value "VALVE2")
      (footprint "CON_3.0_2X_V_DUAL ROW")
      (description "Connector, 3 mm, 2 Contacts")
      (libsource (lib "Fotona") (part "CON2"))
    )
    (comp (ref "X19")
      (value "SWD")
      (footprint "Mlk-pcb:CON-06-MALE-TH-2MM-VERTICAL")
      (description "Connector, 2 mm, 6 Contacts")
      (libsource (lib "Fotona") (part "CON6"))
    )
    (comp (ref "X20")
      (value "FAN2")
      (footprint "MOLEX_47053-1000")
      (description "Connector, 2.54 mm, 4 Contacts")
      (libsource (lib "MA_CONNECT_1") (part "CON 4"))
    )
    (comp (ref "X21")
      (value "BATT")
      (footprint "CON-MOLEX-53047-0210")
      (description "Connector, 1.25 mm, 2 Contacts")
      (libsource (lib "") (part "CON2_1"))
    )
    (comp (ref "X22")
      (value "FLOW")
      (footprint "CON-PH_3PIN_JST")
      (description "Connector, 2 mm, 3 Contacts")
      (libsource (lib "Device") (part "CON3"))
    )
  )
  (nets
    (net (code "1") (name "+3V3") (class "Default")
      (node (ref "C34") (pin "1") (pintype "passive"))
      (node (ref "C35") (pin "1") (pintype "passive"))
      (node (ref "C36") (pin "1") (pintype "passive"))
      (node (ref "C38") (pin "2") (pintype "passive"))
      (node (ref "C39") (pin "2") (pintype "passive"))
      (node (ref "C4") (pin "2") (pintype "passive"))
      (node (ref "C40") (pin "2") (pintype "passive"))
      (node (ref "IC1") (pin "3") (pinfunction "OUT_3") (pintype "power_in"))
      (node (ref "IC8") (pin "100") (pinfunction "Vdd_3_100") (pintype "power_in"))
      (node (ref "IC8") (pin "11") (pinfunction "Vdd_5_11") (pintype "power_in"))
      (node (ref "IC8") (pin "19") (pinfunction "Vdd12_19") (pintype "power_in"))
      (node (ref "IC8") (pin "28") (pinfunction "Vdd_4_28") (pintype "power_in"))
      (node (ref "IC8") (pin "50") (pinfunction "Vdd_1_50") (pintype "power_in"))
      (node (ref "IC8") (pin "75") (pinfunction "Vdd_2_75") (pintype "power_in"))
      (node (ref "V10") (pin "3") (pinfunction "K_3") (pintype "passive"))
      (node (ref "V12") (pin "2") (pinfunction "A2_2") (pintype "passive"))
      (node (ref "V13") (pin "3") (pinfunction "K_3") (pintype "passive"))
      (node (ref "V3") (pin "3") (pinfunction "K_3") (pintype "passive"))
      (node (ref "V9") (pin "3") (pinfunction "K_3") (pintype "passive"))
      (node (ref "X19") (pin "1") (pinfunction "1_1") (pintype "passive"))
    )
    (net (code "2") (name "+5V") (class "Default")
      (node (ref "A2") (pin "5") (pinfunction "Vout_5") (pintype "passive"))
      (node (ref "C15") (pin "2") (pintype "passive"))
      (node (ref "C18") (pin "2") (pintype "passive"))
      (node (ref "C27") (pin "1") (pintype "passive"))
      (node (ref "C3") (pin "2") (pintype "passive"))
      (node (ref "C30") (pin "2") (pintype "passive"))
      (node (ref "C46") (pin "1") (pintype "passive"))
      (node (ref "C59") (pin "P") (pinfunction "P_P") (pintype "passive"))
      (node (ref "C9") (pin "2") (pintype "passive"))
      (node (ref "H1") (pin "A") (pintype "passive"))
      (node (ref "H2") (pin "A") (pintype "passive"))
      (node (ref "H3") (pin "A") (pintype "passive"))
      (node (ref "H4") (pin "A") (pintype "passive"))
      (node (ref "H5") (pin "A") (pintype "passive"))
      (node (ref "H6") (pin "A") (pintype "passive"))
      (node (ref "H7") (pin "A") (pintype "passive"))
      (node (ref "H8") (pin "A") (pintype "passive"))
      (node (ref "IC1") (pin "1") (pinfunction "IN_1") (pintype "power_in"))
      (node (ref "IC10") (pin "16") (pinfunction "VCC_16") (pintype "power_in"))
      (node (ref "IC3") (pin "3") (pinfunction "VCC_3") (pintype "power_in"))
      (node (ref "IC4") (pin "6") (pinfunction "VDD_6") (pintype "power_in"))
      (node (ref "IC6") (pin "8") (pinfunction "VCC_8") (pintype "power_in"))
      (node (ref "JP1") (pin "2") (pintype "passive"))
      (node (ref "L19") (pin "2") (pinfunction "2_2") (pintype "passive"))
      (node (ref "R15") (pin "1") (pintype "passive"))
      (node (ref "R42") (pin "1") (pintype "passive"))
      (node (ref "V14") (pin "E") (pinfunction "E_E") (pintype "passive"))
      (node (ref "V15") (pin "1") (pinfunction "A1_1") (pintype "passive"))
      (node (ref "X16") (pin "7") (pinfunction "7_7") (pintype "passive"))
      (node (ref "X22") (pin "1") (pinfunction "1_1") (pintype "passive"))
      (node (ref "X3") (pin "1") (pinfunction "1_1") (pintype "passive"))
      (node (ref "X4") (pin "1") (pinfunction "1_1") (pintype "passive"))
      (node (ref "X6") (pin "1") (pinfunction "1_1") (pintype "passive"))
      (node (ref "X7") (pin "1") (pinfunction "1_1") (pintype "passive"))
    )
    (net (code "3") (name "+5VA") (class "Default")
      (node (ref "B1") (pin "2") (pinfunction "Vs_2") (pintype "passive"))
      (node (ref "B2") (pin "2") (pinfunction "Vs_2") (pintype "passive"))
      (node (ref "B3") (pin "2") (pinfunction "Vs_2") (pintype "passive"))
      (node (ref "B4") (pin "2") (pinfunction "Vs_2") (pintype "passive"))
      (node (ref "C13") (pin "1") (pintype "passive"))
      (node (ref "C26") (pin "1") (pintype "passive"))
      (node (ref "C49") (pin "1") (pintype "passive"))
      (node (ref "C51") (pin "1") (pintype "passive"))
      (node (ref "C53") (pin "1") (pintype "passive"))
      (node (ref "C55") (pin "1") (pintype "passive"))
      (node (ref "IC11") (pin "4") (pinfunction "OUT_4") (pintype "output"))
    )
    (net (code "4") (name "+12V") (class "Default")
      (node (ref "A1") (pin "5") (pinfunction "Vout_5") (pintype "passive"))
      (node (ref "C2") (pin "2") (pintype "passive"))
      (node (ref "F2") (pin "1") (pintype "passive"))
      (node (ref "JMP1") (pin "3") (pintype "passive"))
      (node (ref "R64") (pin "2") (pintype "passive"))
      (node (ref "X2") (pin "1") (pinfunction "1_1") (pintype "passive"))
    )
    (net (code "5") (name "/12Voff") (class "Default")
      (node (ref "IC8") (pin "92") (pinfunction "PB6//I2C1_SCL_92") (pintype "bidirectional"))
      (node (ref "R5") (pin "1") (pintype "passive"))
    )
    (net (code "6") (name "/AUDIO GND") (class "Default")
      (node (ref "C17") (pin "2") (pintype "passive"))
      (node (ref "X13") (pin "4") (pinfunction "4_4") (pintype "passive"))
    )
    (net (code "7") (name "/AUDIO IN1") (class "Default")
      (node (ref "C16") (pin "2") (pintype "passive"))
      (node (ref "X13") (pin "3") (pinfunction "3_3") (pintype "passive"))
    )
    (net (code "8") (name "/AUDIO IN2") (class "Default")
      (node (ref "X13") (pin "5") (pinfunction "5_5") (pintype "passive"))
    )
    (net (code "9") (name "/BOOT0") (class "Default")
      (node (ref "IC5") (pin "14") (pinfunction "CBUS3_14") (pintype "passive"))
      (node (ref "IC8") (pin "94") (pinfunction "BOOT0_94") (pintype "bidirectional"))
      (node (ref "R49") (pin "1") (pintype "passive"))
    )
    (net (code "10") (name "/BOOT1") (class "Default")
      (node (ref "IC8") (pin "37") (pinfunction "PB2/Boot1_37") (pintype "bidirectional"))
      (node (ref "R48") (pin "2") (pintype "passive"))
    )
    (net (code "11") (name "/CANH") (class "Default")
      (node (ref "IC3") (pin "7") (pinfunction "CANH_7") (pintype "passive"))
      (node (ref "R12") (pin "1") (pintype "passive"))
      (node (ref "X13") (pin "1") (pinfunction "1_1") (pintype "passive"))
      (node (ref "X16") (pin "1") (pinfunction "1_1") (pintype "passive"))
      (node (ref "X6") (pin "3") (pinfunction "3_3") (pintype "passive"))
      (node (ref "X7") (pin "3") (pinfunction "3_3") (pintype "passive"))
    )
    (net (code "12") (name "/CANL") (class "Default")
      (node (ref "IC3") (pin "6") (pinfunction "CANL_6") (pintype "passive"))
      (node (ref "R13") (pin "1") (pintype "passive"))
      (node (ref "X13") (pin "2") (pinfunction "2_2") (pintype "passive"))
      (node (ref "X16") (pin "3") (pinfunction "3_3") (pintype "passive"))
      (node (ref "X6") (pin "5") (pinfunction "5_5") (pintype "passive"))
      (node (ref "X7") (pin "5") (pinfunction "5_5") (pintype "passive"))
    )
    (net (code "13") (name "/CAN_RX") (class "Default")
      (node (ref "IC3") (pin "4") (pinfunction "RX_4") (pintype "output"))
      (node (ref "IC8") (pin "91") (pinfunction "PB5/CAN2_RX_91") (pintype "bidirectional"))
    )
    (net (code "14") (name "/CAN_TX") (class "Default")
      (node (ref "IC3") (pin "1") (pinfunction "TX_1") (pintype "input"))
      (node (ref "IC8") (pin "52") (pinfunction "PB13/CAN2_TX_52") (pintype "bidirectional"))
    )
    (net (code "15") (name "/DIODEsense1") (class "Default")
      (node (ref "IC8") (pin "33") (pinfunction "PC4/ADC12_IN14_33") (pintype "bidirectional"))
      (node (ref "IC8") (pin "53") (pinfunction "PB14/TIM12_CH1_53") (pintype "bidirectional"))
      (node (ref "L13") (pin "1") (pinfunction "1_1") (pintype "passive"))
      (node (ref "V13") (pin "2") (pinfunction "A2_2") (pintype "passive"))
    )
    (net (code "16") (name "/DIODEsense2") (class "Default")
      (node (ref "IC8") (pin "34") (pinfunction "PC5/ADC12_IN15_34") (pintype "bidirectional"))
      (node (ref "IC8") (pin "54") (pinfunction "PB15/TIM12_CH2_54") (pintype "bidirectional"))
      (node (ref "L14") (pin "1") (pinfunction "1_1") (pintype "passive"))
      (node (ref "V13") (pin "1") (pinfunction "A1_1") (pintype "passive"))
    )
    (net (code "17") (name "/DIODEstop") (class "Default")
      (node (ref "L2") (pin "1") (pinfunction "1_1") (pintype "passive"))
      (node (ref "V6") (pin "C") (pinfunction "C_C") (pintype "passive"))
      (node (ref "X6") (pin "2") (pinfunction "2_2") (pintype "passive"))
      (node (ref "X7") (pin "2") (pinfunction "2_2") (pintype "passive"))
    )
    (net (code "18") (name "/DOUT1") (class "Default")
      (node (ref "IC10") (pin "14") (pinfunction "~{DOUT1}_14") (pintype "output"))
      (node (ref "X15") (pin "8") (pinfunction "8_8") (pintype "passive"))
    )
    (net (code "19") (name "/FAN1_tacho") (class "Default")
      (node (ref "IC8") (pin "4") (pinfunction "PE5/TIM9_CH1_4") (pintype "bidirectional"))
      (node (ref "L20") (pin "1") (pinfunction "1_1") (pintype "passive"))
      (node (ref "V1") (pin "4") (pinfunction "4_4") (pintype "passive"))
    )
    (net (code "20") (name "/FAN2_tacho") (class "Default")
      (node (ref "IC8") (pin "5") (pinfunction "PE6/TIM9_CH2_5") (pintype "bidirectional"))
      (node (ref "L17") (pin "1") (pinfunction "1_1") (pintype "passive"))
      (node (ref "V1") (pin "5") (pinfunction "5_5") (pintype "passive"))
    )
    (net (code "21") (name "/FAN_RPM") (class "Default")
      (node (ref "IC8") (pin "95") (pinfunction "PB8/TIM10_CH1_95") (pintype "bidirectional"))
      (node (ref "L22") (pin "1") (pinfunction "1_1") (pintype "passive"))
      (node (ref "R63") (pin "1") (pintype "passive"))
      (node (ref "V1") (pin "1") (pinfunction "1_1") (pintype "passive"))
    )
    (net (code "22") (name "/FLOW_tacho") (class "Default")
      (node (ref "IC8") (pin "32") (pinfunction "PA7/ADC12_IN7/TIM3_CH2_32") (pintype "bidirectional"))
      (node (ref "L18") (pin "1") (pinfunction "1_1") (pintype "passive"))
      (node (ref "V16") (pin "4") (pinfunction "4_4") (pintype "passive"))
    )
    (net (code "23") (name "/FOOTSWactive") (class "Default")
      (node (ref "R9") (pin "1") (pintype "passive"))
      (node (ref "X15") (pin "5") (pinfunction "5_5") (pintype "passive"))
      (node (ref "X16") (pin "6") (pinfunction "6_6") (pintype "passive"))
      (node (ref "X6") (pin "6") (pinfunction "6_6") (pintype "passive"))
      (node (ref "X7") (pin "6") (pinfunction "6_6") (pintype "passive"))
    )
    (net (code "24") (name "/LED_1") (class "Default")
      (node (ref "IC8") (pin "59") (pinfunction "PD12/TIM4_CH1_59") (pintype "bidirectional"))
      (node (ref "R50") (pin "1") (pintype "passive"))
    )
    (net (code "25") (name "/LED_2") (class "Default")
      (node (ref "IC8") (pin "60") (pinfunction "PD13/TIM4_CH2_60") (pintype "bidirectional"))
      (node (ref "R51") (pin "1") (pintype "passive"))
    )
    (net (code "26") (name "/LED_BLUE1") (class "Default")
      (node (ref "IC8") (pin "84") (pinfunction "PD3_84") (pintype "bidirectional"))
      (node (ref "R30") (pin "1") (pintype "passive"))
    )
    (net (code "27") (name "/LED_BLUE2") (class "Default")
      (node (ref "IC8") (pin "88") (pinfunction "PD7_88") (pintype "bidirectional"))
      (node (ref "R34") (pin "1") (pintype "passive"))
    )
    (net (code "28") (name "/LED_GREEN1") (class "Default")
      (node (ref "IC8") (pin "82") (pinfunction "PD1_82") (pintype "bidirectional"))
      (node (ref "R28") (pin "1") (pintype "passive"))
    )
    (net (code "29") (name "/LED_GREEN2") (class "Default")
      (node (ref "IC8") (pin "86") (pinfunction "PD5_86") (pintype "bidirectional"))
      (node (ref "R32") (pin "1") (pintype "passive"))
    )
    (net (code "30") (name "/LED_RED1") (class "Default")
      (node (ref "IC8") (pin "81") (pinfunction "PD0_81") (pintype "bidirectional"))
      (node (ref "R27") (pin "1") (pintype "passive"))
    )
    (net (code "31") (name "/LED_RED2") (class "Default")
      (node (ref "IC8") (pin "85") (pinfunction "PD4_85") (pintype "bidirectional"))
      (node (ref "R31") (pin "1") (pintype "passive"))
    )
    (net (code "32") (name "/LED_YELLOW1") (class "Default")
      (node (ref "IC8") (pin "83") (pinfunction "PD2_83") (pintype "bidirectional"))
      (node (ref "R29") (pin "1") (pintype "passive"))
    )
    (net (code "33") (name "/LED_YELLOW2") (class "Default")
      (node (ref "IC8") (pin "87") (pinfunction "PD6_87") (pintype "bidirectional"))
      (node (ref "R33") (pin "1") (pintype "passive"))
    )
    (net (code "34") (name "/MCO") (class "Default")
      (node (ref "C45") (pin "2") (pintype "passive"))
      (node (ref "G1") (pin "2") (pinfunction "OSC2_2") (pintype "passive"))
      (node (ref "IC8") (pin "12") (pinfunction "OSC_IN_12") (pintype "input"))
    )
    (net (code "35") (name "/NRST") (class "Default")
      (node (ref "C31") (pin "1") (pintype "passive"))
      (node (ref "IC5") (pin "13") (pinfunction "CBUS2_13") (pintype "passive"))
      (node (ref "IC8") (pin "14") (pinfunction "NRST_14") (pintype "bidirectional"))
      (node (ref "X19") (pin "5") (pinfunction "5_5") (pintype "passive"))
    )
    (net (code "36") (name "/PUMP_CSENSE") (class "Default")
      (node (ref "IC8") (pin "23") (pinfunction "PA0/ADC123_IN0_23") (pintype "bidirectional"))
      (node (ref "R6") (pin "2") (pintype "passive"))
      (node (ref "V3") (pin "1") (pinfunction "A1_1") (pintype "passive"))
      (node (ref "V3") (pin "2") (pinfunction "A2_2") (pintype "passive"))
    )
    (net (code "37") (name "/PUMP_RPM") (class "Default")
      (node (ref "IC6") (pin "5") (pintype "input"))
      (node (ref "IC8") (pin "29") (pinfunction "PA4/DAC_OUT1/ADC12_IN4_29") (pintype "bidirectional"))
      (node (ref "R4") (pin "2") (pintype "passive"))
    )
    (net (code "38") (name "/PUMP_tacho") (class "Default")
      (node (ref "IC8") (pin "31") (pinfunction "PA6/ADC12_IN6/TIM3_CH1_31") (pintype "bidirectional"))
      (node (ref "V8") (pin "C") (pintype "passive"))
    )
    (net (code "39") (name "/Psense0") (class "Default")
      (node (ref "C50") (pin "1") (pintype "passive"))
      (node (ref "IC8") (pin "15") (pinfunction "PC0/ADC123_IN10_15") (pintype "bidirectional"))
      (node (ref "R55") (pin "1") (pintype "passive"))
      (node (ref "R56") (pin "2") (pintype "passive"))
    )
    (net (code "40") (name "/Psense1") (class "Default")
      (node (ref "C52") (pin "1") (pintype "passive"))
      (node (ref "IC8") (pin "16") (pinfunction "PC1/ADC123_IN11_16") (pintype "bidirectional"))
      (node (ref "R57") (pin "1") (pintype "passive"))
      (node (ref "R58") (pin "2") (pintype "passive"))
    )
    (net (code "41") (name "/Psense2") (class "Default")
      (node (ref "C54") (pin "1") (pintype "passive"))
      (node (ref "IC8") (pin "17") (pinfunction "PC2/ADC123_IN12_17") (pintype "bidirectional"))
      (node (ref "R59") (pin "1") (pintype "passive"))
      (node (ref "R60") (pin "2") (pintype "passive"))
    )
    (net (code "42") (name "/Psense3") (class "Default")
      (node (ref "C56") (pin "1") (pintype "passive"))
      (node (ref "IC8") (pin "18") (pinfunction "PC3/ADC123_IN13_18") (pintype "bidirectional"))
      (node (ref "R61") (pin "1") (pintype "passive"))
      (node (ref "R62") (pin "2") (pintype "passive"))
    )
    (net (code "43") (name "/RIN1") (class "Default")
      (node (ref "IC10") (pin "13") (pinfunction "RIN1_13") (pintype "input"))
      (node (ref "X15") (pin "7") (pinfunction "7_7") (pintype "passive"))
    )
    (net (code "44") (name "/SWCLK") (class "Default")
      (node (ref "IC8") (pin "76") (pinfunction "PA14_76") (pintype "bidirectional"))
      (node (ref "X19") (pin "2") (pinfunction "2_2") (pintype "passive"))
    )
    (net (code "45") (name "/SWDIO") (class "Default")
      (node (ref "IC8") (pin "72") (pinfunction "PA13_72") (pintype "bidirectional"))
      (node (ref "X19") (pin "4") (pinfunction "4_4") (pintype "passive"))
    )
    (net (code "46") (name "/SWO") (class "Default")
      (node (ref "IC8") (pin "89") (pinfunction "PB3/TIM2_CH2_89") (pintype "bidirectional"))
      (node (ref "X19") (pin "6") (pinfunction "6_6") (pintype "passive"))
    )
    (net (code "47") (name "/SYS_SHG") (class "Default")
      (node (ref "IC8") (pin "90") (pinfunction "PB4_90") (pintype "bidirectional"))
      (node (ref "R14") (pin "2") (pintype "passive"))
    )
    (net (code "48") (name "/TIM1_CH1") (class "Default")
      (node (ref "IC7") (pin "4") (pinfunction "I3_4") (pintype "passive"))
      (node (ref "IC8") (pin "40") (pinfunction "PE9/TIM1_CH1_40") (pintype "bidirectional"))
    )
    (net (code "49") (name "/TIM1_CH2") (class "Default")
      (node (ref "IC7") (pin "3") (pinfunction "I2_3") (pintype "passive"))
      (node (ref "IC8") (pin "42") (pinfunction "PE11/TIM1_CH2_42") (pintype "bidirectional"))
    )
    (net (code "50") (name "/TIM1_CH3") (class "Default")
      (node (ref "IC7") (pin "2") (pinfunction "I1_2") (pintype "passive"))
      (node (ref "IC8") (pin "44") (pinfunction "PE13/TIM1_CH3_44") (pintype "bidirectional"))
    )
    (net (code "51") (name "/TIM1_CH4") (class "Default")
      (node (ref "IC7") (pin "1") (pinfunction "I0_1") (pintype "passive"))
      (node (ref "IC8") (pin "45") (pinfunction "PE14/TIM1_CH4_45") (pintype "bidirectional"))
    )
    (net (code "52") (name "/TIM8_CH1") (class "Default")
      (node (ref "IC7") (pin "5") (pinfunction "I4_5") (pintype "passive"))
      (node (ref "IC8") (pin "63") (pinfunction "PC6/TIM8_CH1_63") (pintype "bidirectional"))
    )
    (net (code "53") (name "/TIM8_CH2") (class "Default")
      (node (ref "IC7") (pin "6") (pinfunction "I5_6") (pintype "passive"))
      (node (ref "IC8") (pin "64") (pinfunction "PC7/TIM8_CH2_64") (pintype "bidirectional"))
    )
    (net (code "54") (name "/TIM8_CH3") (class "Default")
      (node (ref "IC7") (pin "7") (pinfunction "I6_7") (pintype "passive"))
      (node (ref "IC8") (pin "65") (pinfunction "PC8/TIM8_CH3_65") (pintype "bidirectional"))
    )
    (net (code "55") (name "/TIM8_CH4") (class "Default")
      (node (ref "IC7") (pin "8") (pinfunction "I7_8") (pintype "passive"))
      (node (ref "IC8") (pin "66") (pinfunction "PC9/TIM8_CH4_66") (pintype "bidirectional"))
    )
    (net (code "56") (name "/TempH2O_1") (class "Default")
      (node (ref "C47") (pin "1") (pintype "passive"))
      (node (ref "IC8") (pin "24") (pinfunction "PA1/ADC123_IN1_24") (pintype "bidirectional"))
      (node (ref "R53") (pin "1") (pintype "passive"))
      (node (ref "X17") (pin "1") (pinfunction "1_1") (pintype "passive"))
    )
    (net (code "57") (name "/TempH2O_2") (class "Default")
      (node (ref "C48") (pin "1") (pintype "passive"))
      (node (ref "IC8") (pin "25") (pinfunction "PA2/ADC123_IN2_25") (pintype "bidirectional"))
      (node (ref "R54") (pin "1") (pintype "passive"))
      (node (ref "X17") (pin "3") (pinfunction "3_3") (pintype "passive"))
    )
    (net (code "58") (name "/UART0_RXD") (class "Default")
      (node (ref "JP2") (pin "1") (pintype "passive"))
      (node (ref "X13") (pin "7") (pinfunction "7_7") (pintype "passive"))
    )
    (net (code "59") (name "/UART0_TXD") (class "Default")
      (node (ref "JP3") (pin "1") (pintype "passive"))
      (node (ref "X13") (pin "8") (pinfunction "8_8") (pintype "passive"))
    )
    (net (code "60") (name "/USART1_RX") (class "Default")
      (node (ref "IC8") (pin "69") (pinfunction "PA10/USART1_RX_69") (pintype "bidirectional"))
      (node (ref "JP2") (pin "3") (pintype "passive"))
    )
    (net (code "61") (name "/USART1_TX") (class "Default")
      (node (ref "IC8") (pin "68") (pinfunction "PA9/USART1_TX_68") (pintype "bidirectional"))
      (node (ref "JP3") (pin "3") (pintype "passive"))
    )
    (net (code "62") (name "/USART3_RX") (class "Default")
      (node (ref "IC10") (pin "12") (pinfunction "~{ROUT1}_12") (pintype "output"))
      (node (ref "IC8") (pin "79") (pinfunction "PC11/USART3_RX_79") (pintype "bidirectional"))
    )
    (net (code "63") (name "/USART3_TX") (class "Default")
      (node (ref "IC10") (pin "11") (pinfunction "DIN1_11") (pintype "input"))
      (node (ref "IC8") (pin "78") (pinfunction "PC10/USART3_TX_78") (pintype "bidirectional"))
    )
    (net (code "64") (name "/USBDM") (class "Default")
      (node (ref "C22") (pin "2") (pintype "passive"))
      (node (ref "IC5") (pin "16") (pinfunction "USBDM_16") (pintype "passive"))
      (node (ref "R20") (pin "1") (pintype "passive"))
    )
    (net (code "65") (name "/USBDP") (class "Default")
      (node (ref "C24") (pin "1") (pintype "passive"))
      (node (ref "IC5") (pin "15") (pinfunction "USBDP_15") (pintype "passive"))
      (node (ref "R21") (pin "1") (pintype "passive"))
    )
    (net (code "66") (name "/USBPWR#") (class "Default")
      (node (ref "IC5") (pin "12") (pinfunction "CBUS4_12") (pintype "passive"))
      (node (ref "R26") (pin "2") (pintype "passive"))
    )
    (net (code "67") (name "/USB_RXLED") (class "Default")
      (node (ref "IC5") (pin "22") (pinfunction "CBUS1_22") (pintype "passive"))
      (node (ref "R25") (pin "2") (pintype "passive"))
    )
    (net (code "68") (name "/USB_TXLED") (class "Default")
      (node (ref "IC5") (pin "23") (pinfunction "CBUS0_23") (pintype "passive"))
      (node (ref "R24") (pin "2") (pintype "passive"))
    )
    (net (code "69") (name "/cwbBUTTON") (class "Default")
      (node (ref "L12") (pin "1") (pinfunction "1_1") (pintype "passive"))
      (node (ref "R36") (pin "1") (pintype "passive"))
      (node (ref "V11") (pin "1") (pinfunction "1_1") (pintype "passive"))
      (node (ref "V6") (pin "E") (pinfunction "E_E") (pintype "passive"))
    )
    (net (code "70") (name "/cwbDOOR") (class "Default")
      (node (ref "L1") (pin "1") (pinfunction "1_1") (pintype "passive"))
      (node (ref "L16") (pin "1") (pinfunction "1_1") (pintype "passive"))
      (node (ref "R37") (pin "1") (pintype "passive"))
      (node (ref "V11") (pin "3") (pinfunction "3_3") (pintype "passive"))
    )
    (net (code "71") (name "/cwbENGM") (class "Default")
      (node (ref "L15") (pin "1") (pinfunction "1_1") (pintype "passive"))
      (node (ref "L21") (pin "1") (pinfunction "1_1") (pintype "passive"))
      (node (ref "R38") (pin "1") (pintype "passive"))
      (node (ref "V14") (pin "C") (pinfunction "C_C") (pintype "passive"))
      (node (ref "V4") (pin "5") (pinfunction "5_5") (pintype "passive"))
    )
    (net (code "72") (name "/cwbENGMovride") (class "Default")
      (node (ref "IC8") (pin "67") (pinfunction "PA8_67") (pintype "bidirectional"))
      (node (ref "R16") (pin "2") (pintype "passive"))
    )
    (net (code "73") (name "24V") (class "Default")
      (node (ref "A1") (pin "2") (pinfunction "Vin_2") (pintype "passive"))
      (node (ref "A2") (pin "2") (pinfunction "Vin_2") (pintype "passive"))
      (node (ref "C1") (pin "1") (pintype "passive"))
      (node (ref "C25") (pin "1") (pintype "passive"))
      (node (ref "C29") (pin "1") (pintype "passive"))
      (node (ref "F1") (pin "2") (pinfunction "2_2") (pintype "passive"))
      (node (ref "IC7") (pin "10") (pinfunction "PWR_10") (pintype "passive"))
      (node (ref "JMP1") (pin "1") (pintype "passive"))
      (node (ref "R46") (pin "2") (pintype "passive"))
      (node (ref "R7") (pin "2") (pintype "passive"))
      (node (ref "X10") (pin "5") (pinfunction "5_5") (pintype "passive"))
      (node (ref "X11") (pin "2") (pinfunction "2_2") (pintype "passive"))
      (node (ref "X11") (pin "4") (pinfunction "4_4") (pintype "passive"))
      (node (ref "X11") (pin "6") (pinfunction "6_6") (pintype "passive"))
      (node (ref "X11") (pin "8") (pinfunction "8_8") (pintype "passive"))
      (node (ref "X12") (pin "2") (pinfunction "2_2") (pintype "passive"))
      (node (ref "X12") (pin "4") (pinfunction "4_4") (pintype "passive"))
      (node (ref "X12") (pin "6") (pinfunction "6_6") (pintype "passive"))
      (node (ref "X18") (pin "1") (pinfunction "1_1") (pintype "passive"))
    )
    (net (code "74") (name "Agnd") (class "Default")
      (node (ref "B1") (pin "3") (pinfunction "GND_3") (pintype "passive"))
      (node (ref "B2") (pin "3") (pinfunction "GND_3") (pintype "passive"))
      (node (ref "B3") (pin "3") (pinfunction "GND_3") (pintype "passive"))
      (node (ref "B4") (pin "3") (pinfunction "GND_3") (pintype "passive"))
      (node (ref "C12") (pin "2") (pintype "passive"))
      (node (ref "C26") (pin "2") (pintype "passive"))
      (node (ref "C41") (pin "2") (pintype "passive"))
      (node (ref "C42") (pin "2") (pintype "passive"))
      (node (ref "C43") (pin "2") (pintype "passive"))
      (node (ref "C47") (pin "2") (pintype "passive"))
      (node (ref "C48") (pin "2") (pintype "passive"))
      (node (ref "C49") (pin "2") (pintype "passive"))
      (node (ref "C50") (pin "2") (pintype "passive"))
      (node (ref "C51") (pin "2") (pintype "passive"))
      (node (ref "C52") (pin "2") (pintype "passive"))
      (node (ref "C53") (pin "2") (pintype "passive"))
      (node (ref "C54") (pin "2") (pintype "passive"))
      (node (ref "C55") (pin "2") (pintype "passive"))
      (node (ref "C56") (pin "2") (pintype "passive"))
      (node (ref "IC11") (pin "1") (pinfunction "GND_1") (pintype "passive"))
      (node (ref "IC8") (pin "20") (pinfunction "VssA_20") (pintype "input"))
      (node (ref "IC9") (pin "3") (pinfunction "GND_3") (pintype "power_in"))
      (node (ref "J4") (pin "2") (pintype "passive"))
      (node (ref "R43") (pin "1") (pintype "passive"))
      (node (ref "R45") (pin "2") (pintype "passive"))
      (node (ref "R47") (pin "1") (pintype "passive"))
      (node (ref "R56") (pin "1") (pintype "passive"))
      (node (ref "R58") (pin "1") (pintype "passive"))
      (node (ref "R60") (pin "1") (pintype "passive"))
      (node (ref "R62") (pin "1") (pintype "passive"))
      (node (ref "X17") (pin "2") (pinfunction "2_2") (pintype "passive"))
      (node (ref "X17") (pin "4") (pinfunction "4_4") (pintype "passive"))
    )
    (net (code "75") (name "EARTH") (class "Default")
      (node (ref "J2") (pin "2") (pintype "passive"))
      (node (ref "J3") (pin "1") (pintype "passive"))
      (node (ref "TP2") (pin "1") (pinfunction "1_1") (pintype "passive"))
    )
    (net (code "76") (name "GND") (class "Default")
      (node (ref "C10") (pin "2") (pintype "passive"))
      (node (ref "C11") (pin "2") (pintype "passive"))
      (node (ref "C14") (pin "1") (pintype "passive"))
      (node (ref "C15") (pin "1") (pintype "passive"))
      (node (ref "C18") (pin "1") (pintype "passive"))
      (node (ref "C19") (pin "2") (pintype "passive"))
      (node (ref "C20") (pin "2") (pintype "passive"))
      (node (ref "C21") (pin "1") (pintype "passive"))
      (node (ref "C22") (pin "1") (pintype "passive"))
      (node (ref "C23") (pin "1") (pintype "passive"))
      (node (ref "C24") (pin "2") (pintype "passive"))
      (node (ref "C27") (pin "2") (pintype "passive"))
      (node (ref "C3") (pin "1") (pintype "passive"))
      (node (ref "C30") (pin "1") (pintype "passive"))
      (node (ref "C31") (pin "2") (pintype "passive"))
      (node (ref "C32") (pin "2") (pintype "passive"))
      (node (ref "C33") (pin "2") (pintype "passive"))
      (node (ref "C34") (pin "2") (pintype "passive"))
      (node (ref "C35") (pin "2") (pintype "passive"))
      (node (ref "C36") (pin "2") (pintype "passive"))
      (node (ref "C37") (pin "2") (pintype "passive"))
      (node (ref "C38") (pin "1") (pintype "passive"))
      (node (ref "C39") (pin "1") (pintype "passive"))
      (node (ref "C4") (pin "1") (pintype "passive"))
      (node (ref "C40") (pin "1") (pintype "passive"))
      (node (ref "C44") (pin "1") (pintype "passive"))
      (node (ref "C45") (pin "1") (pintype "passive"))
      (node (ref "C46") (pin "2") (pintype "passive"))
      (node (ref "C57") (pin "2") (pintype "passive"))
      (node (ref "C58") (pin "2") (pintype "passive"))
      (node (ref "C59") (pin "M") (pinfunction "M_M") (pintype "passive"))
      (node (ref "C7") (pin "1") (pintype "passive"))
      (node (ref "C8") (pin "1") (pintype "passive"))
      (node (ref "C9") (pin "1") (pintype "passive"))
      (node (ref "G3") (pin "M") (pinfunction "-_M") (pintype "passive"))
      (node (ref "IC1") (pin "2") (pinfunction "GND_2") (pintype "power_in"))
      (node (ref "IC10") (pin "15") (pinfunction "GND_15") (pintype "power_in"))
      (node (ref "IC2") (pin "11") (pinfunction "E_11") (pintype "passive"))
      (node (ref "IC2") (pin "13") (pinfunction "E_13") (pintype "passive"))
      (node (ref "IC2") (pin "15") (pinfunction "E_15") (pintype "passive"))
      (node (ref "IC2") (pin "9") (pinfunction "E_9") (pintype "passive"))
      (node (ref "IC3") (pin "2") (pinfunction "GND_2") (pintype "power_in"))
      (node (ref "IC3") (pin "8") (pinfunction "STB_8") (pintype "input"))
      (node (ref "IC4") (pin "2") (pinfunction "NC_2") (pintype "passive"))
      (node (ref "IC4") (pin "7") (pinfunction "GND_7") (pintype "power_in"))
      (node (ref "IC4") (pin "9") (pinfunction "EP_9") (pintype "power_in"))
      (node (ref "IC5") (pin "18") (pinfunction "GND_18") (pintype "passive"))
      (node (ref "IC5") (pin "21") (pinfunction "GND_21") (pintype "passive"))
      (node (ref "IC5") (pin "25") (pinfunction "AGND_25") (pintype "passive"))
      (node (ref "IC5") (pin "26") (pinfunction "TEST_26") (pintype "passive"))
      (node (ref "IC5") (pin "7") (pinfunction "GND_7") (pintype "passive"))
      (node (ref "IC6") (pin "4") (pinfunction "VEE_4") (pintype "power_in"))
      (node (ref "IC8") (pin "10") (pinfunction "Vss_5_10") (pintype "power_in"))
      (node (ref "IC8") (pin "27") (pinfunction "Vss_4_27") (pintype "power_in"))
      (node (ref "IC8") (pin "74") (pinfunction "Vss_2_74") (pintype "power_in"))
      (node (ref "IC8") (pin "99") (pinfunction "RFU_99") (pintype "passive"))
      (node (ref "J3") (pin "2") (pintype "passive"))
      (node (ref "J4") (pin "1") (pintype "passive"))
      (node (ref "R23") (pin "1") (pintype "passive"))
      (node (ref "R3") (pin "2") (pintype "passive"))
      (node (ref "R4") (pin "1") (pintype "passive"))
      (node (ref "R48") (pin "1") (pintype "passive"))
      (node (ref "R49") (pin "2") (pintype "passive"))
      (node (ref "V11") (pin "2") (pinfunction "2_2") (pintype "passive"))
      (node (ref "V16") (pin "2") (pinfunction "2_2") (pintype "passive"))
      (node (ref "V4") (pin "2") (pinfunction "2_2") (pintype "passive"))
      (node (ref "V7") (pin "2") (pinfunction "2_2") (pintype "passive"))
      (node (ref "X13") (pin "6") (pinfunction "6_6") (pintype "passive"))
      (node (ref "X16") (pin "4") (pinfunction "4_4") (pintype "passive"))
      (node (ref "X19") (pin "3") (pinfunction "3_3") (pintype "passive"))
      (node (ref "X21") (pin "2") (pinfunction "2_2") (pintype "passive"))
      (node (ref "X22") (pin "3") (pinfunction "3_3") (pintype "passive"))
      (node (ref "X3") (pin "3") (pinfunction "3_3") (pintype "passive"))
      (node (ref "X4") (pin "3") (pinfunction "3_3") (pintype "passive"))
      (node (ref "X6") (pin "4") (pinfunction "4_4") (pintype "passive"))
      (node (ref "X7") (pin "4") (pinfunction "4_4") (pintype "passive"))
      (node (ref "X9") (pin "5") (pinfunction "5_5") (pintype "passive"))
      (node (ref "X9") (pin "6") (pinfunction "6_6") (pintype "passive"))
    )
    (net (code "77") (name "Net-(A1-ON{slash}OFF)") (class "Default")
      (node (ref "A1") (pin "1") (pinfunction "ON/OFF_1") (pintype "passive"))
      (node (ref "V2") (pin "C") (pintype "passive"))
    )
    (net (code "78") (name "Net-(A1-TRIM)") (class "Default")
      (node (ref "A1") (pin "4") (pinfunction "TRIM_4") (pintype "passive"))
      (node (ref "R1") (pin "1") (pintype "passive"))
    )
    (net (code "79") (name "Net-(B1-OUT)") (class "Default")
      (node (ref "B1") (pin "4") (pinfunction "OUT_4") (pintype "passive"))
      (node (ref "R55") (pin "2") (pintype "passive"))
    )
    (net (code "80") (name "Net-(B2-OUT)") (class "Default")
      (node (ref "B2") (pin "4") (pinfunction "OUT_4") (pintype "passive"))
      (node (ref "R57") (pin "2") (pintype "passive"))
    )
    (net (code "81") (name "Net-(B3-OUT)") (class "Default")
      (node (ref "B3") (pin "4") (pinfunction "OUT_4") (pintype "passive"))
      (node (ref "R59") (pin "2") (pintype "passive"))
    )
    (net (code "82") (name "Net-(B4-OUT)") (class "Default")
      (node (ref "B4") (pin "4") (pinfunction "OUT_4") (pintype "passive"))
      (node (ref "R61") (pin "2") (pintype "passive"))
    )
    (net (code "83") (name "Net-(C10-Pad1)") (class "Default")
      (node (ref "C10") (pin "1") (pintype "passive"))
      (node (ref "R50") (pin "2") (pintype "passive"))
      (node (ref "X3") (pin "2") (pinfunction "2_2") (pintype "passive"))
    )
    (net (code "84") (name "Net-(C11-Pad1)") (class "Default")
      (node (ref "C11") (pin "1") (pintype "passive"))
      (node (ref "R51") (pin "2") (pintype "passive"))
      (node (ref "X4") (pin "2") (pinfunction "2_2") (pintype "passive"))
    )
    (net (code "85") (name "Net-(C19-Pad1)") (class "Default")
      (node (ref "C19") (pin "1") (pintype "passive"))
      (node (ref "L3") (pin "1") (pinfunction "1_1") (pintype "passive"))
      (node (ref "R22") (pin "1") (pintype "passive"))
      (node (ref "V7") (pin "4") (pinfunction "4_4") (pintype "passive"))
      (node (ref "X9") (pin "1") (pinfunction "1_1") (pintype "passive"))
    )
    (net (code "86") (name "Net-(C28-Pad1)") (class "Default")
      (node (ref "C28") (pin "1") (pintype "passive"))
      (node (ref "IC6") (pin "1") (pintype "output"))
      (node (ref "R41") (pin "2") (pintype "passive"))
      (node (ref "R6") (pin "1") (pintype "passive"))
    )
    (net (code "87") (name "Net-(C28-Pad2)") (class "Default")
      (node (ref "C28") (pin "2") (pintype "passive"))
      (node (ref "IC6") (pin "2") (pintype "input"))
      (node (ref "R40") (pin "2") (pintype "passive"))
      (node (ref "R41") (pin "1") (pintype "passive"))
    )
    (net (code "88") (name "Net-(F1-Pad1)") (class "Default")
      (node (ref "F1") (pin "1") (pinfunction "1_1") (pintype "passive"))
      (node (ref "X1") (pin "1") (pinfunction "1_1") (pintype "passive"))
      (node (ref "X1") (pin "3") (pinfunction "3_3") (pintype "passive"))
    )
    (net (code "89") (name "Net-(F2-Pad2)") (class "Default")
      (node (ref "F2") (pin "2") (pintype "passive"))
      (node (ref "IC2") (pin "1") (pinfunction "A_1") (pintype "passive"))
      (node (ref "IC2") (pin "3") (pinfunction "A_3") (pintype "passive"))
      (node (ref "IC2") (pin "5") (pinfunction "A_5") (pintype "passive"))
      (node (ref "IC2") (pin "7") (pinfunction "A_7") (pintype "passive"))
      (node (ref "R44") (pin "2") (pintype "passive"))
      (node (ref "X15") (pin "1") (pinfunction "1_1") (pintype "passive"))
    )
    (net (code "90") (name "Net-(G1-OSC1)") (class "Default")
      (node (ref "C44") (pin "2") (pintype "passive"))
      (node (ref "G1") (pin "1") (pinfunction "OSC1_1") (pintype "passive"))
      (node (ref "R52") (pin "1") (pintype "passive"))
    )
    (net (code "91") (name "Net-(G3-+)") (class "Default")
      (node (ref "G3") (pin "P") (pinfunction "+_P") (pintype "passive"))
      (node (ref "V12") (pin "1") (pinfunction "A1_1") (pintype "passive"))
      (node (ref "X21") (pin "1") (pinfunction "1_1") (pintype "passive"))
    )
    (net (code "92") (name "Net-(H1-PadK)") (class "Default")
      (node (ref "H1") (pin "K") (pintype "passive"))
      (node (ref "R27") (pin "2") (pintype "passive"))
    )
    (net (code "93") (name "Net-(H2-PadK)") (class "Default")
      (node (ref "H2") (pin "K") (pintype "passive"))
      (node (ref "R28") (pin "2") (pintype "passive"))
    )
    (net (code "94") (name "Net-(H3-PadK)") (class "Default")
      (node (ref "H3") (pin "K") (pintype "passive"))
      (node (ref "R29") (pin "2") (pintype "passive"))
    )
    (net (code "95") (name "Net-(H4-PadK)") (class "Default")
      (node (ref "H4") (pin "K") (pintype "passive"))
      (node (ref "R30") (pin "2") (pintype "passive"))
    )
    (net (code "96") (name "Net-(H5-PadK)") (class "Default")
      (node (ref "H5") (pin "K") (pintype "passive"))
      (node (ref "R31") (pin "2") (pintype "passive"))
    )
    (net (code "97") (name "Net-(H6-PadK)") (class "Default")
      (node (ref "H6") (pin "K") (pintype "passive"))
      (node (ref "R32") (pin "2") (pintype "passive"))
    )
    (net (code "98") (name "Net-(H7-PadK)") (class "Default")
      (node (ref "H7") (pin "K") (pintype "passive"))
      (node (ref "R33") (pin "2") (pintype "passive"))
    )
    (net (code "99") (name "Net-(H8-PadK)") (class "Default")
      (node (ref "H8") (pin "K") (pintype "passive"))
      (node (ref "R34") (pin "2") (pintype "passive"))
    )
    (net (code "100") (name "Net-(H9-PadK)") (class "Default")
      (node (ref "H9") (pin "K") (pinfunction "K_K") (pintype "passive"))
      (node (ref "R24") (pin "1") (pintype "passive"))
    )
    (net (code "101") (name "Net-(H10-PadK)") (class "Default")
      (node (ref "H10") (pin "K") (pinfunction "K_K") (pintype "passive"))
      (node (ref "R25") (pin "1") (pintype "passive"))
    )
    (net (code "102") (name "Net-(H11-PadK)") (class "Default")
      (node (ref "H11") (pin "K") (pinfunction "K_K") (pintype "passive"))
      (node (ref "R26") (pin "1") (pintype "passive"))
    )
    (net (code "103") (name "Net-(H12-PadA)") (class "Default")
      (node (ref "H12") (pin "A") (pintype "passive"))
      (node (ref "V5") (pin "A") (pintype "passive"))
    )
    (net (code "104") (name "Net-(IC2-K-Pad2)") (class "Default")
      (node (ref "IC2") (pin "2") (pinfunction "K_2") (pintype "passive"))
      (node (ref "R8") (pin "2") (pintype "passive"))
    )
    (net (code "105") (name "Net-(IC2-K-Pad4)") (class "Default")
      (node (ref "IC2") (pin "4") (pinfunction "K_4") (pintype "passive"))
      (node (ref "R9") (pin "2") (pintype "passive"))
    )
    (net (code "106") (name "Net-(IC2-K-Pad6)") (class "Default")
      (node (ref "IC2") (pin "6") (pinfunction "K_6") (pintype "passive"))
      (node (ref "R10") (pin "2") (pintype "passive"))
    )
    (net (code "107") (name "Net-(IC2-K-Pad8)") (class "Default")
      (node (ref "IC2") (pin "8") (pinfunction "K_8") (pintype "passive"))
      (node (ref "R11") (pin "2") (pintype "passive"))
    )
    (net (code "108") (name "Net-(IC3-SPLIT)") (class "Default")
      (node (ref "C14") (pin "2") (pintype "passive"))
      (node (ref "IC3") (pin "5") (pinfunction "SPLIT_5") (pintype "passive"))
      (node (ref "R12") (pin "2") (pintype "passive"))
      (node (ref "R13") (pin "2") (pintype "passive"))
    )
    (net (code "109") (name "Net-(IC4-IN+)") (class "Default")
      (node (ref "C16") (pin "1") (pintype "passive"))
      (node (ref "IC4") (pin "3") (pinfunction "IN+_3") (pintype "input"))
    )
    (net (code "110") (name "Net-(IC4-IN-)") (class "Default")
      (node (ref "C17") (pin "1") (pintype "passive"))
      (node (ref "IC4") (pin "4") (pinfunction "IN-_4") (pintype "input"))
    )
    (net (code "111") (name "Net-(IC4-OUT+)") (class "Default")
      (node (ref "IC4") (pin "5") (pinfunction "OUT+_5") (pintype "output"))
      (node (ref "X8") (pin "1") (pinfunction "1_1") (pintype "passive"))
    )
    (net (code "112") (name "Net-(IC4-OUT-)") (class "Default")
      (node (ref "IC4") (pin "8") (pinfunction "OUT-_8") (pintype "passive"))
      (node (ref "X8") (pin "3") (pinfunction "3_3") (pintype "passive"))
    )
    (net (code "113") (name "Net-(IC4-~{SD})") (class "Default")
      (node (ref "IC4") (pin "1") (pinfunction "~{SD}_1") (pintype "passive"))
      (node (ref "R15") (pin "2") (pintype "passive"))
    )
    (net (code "114") (name "Net-(IC5-RXD)") (class "Default")
      (node (ref "IC5") (pin "5") (pinfunction "RXD_5") (pintype "passive"))
      (node (ref "JP3") (pin "2") (pintype "passive"))
    )
    (net (code "115") (name "Net-(IC5-TXD)") (class "Default")
      (node (ref "IC5") (pin "1") (pinfunction "TXD_1") (pintype "passive"))
      (node (ref "JP2") (pin "2") (pintype "passive"))
    )
    (net (code "116") (name "Net-(IC5-VCC)") (class "Default")
      (node (ref "C20") (pin "1") (pintype "passive"))
      (node (ref "C21") (pin "2") (pintype "passive"))
      (node (ref "IC5") (pin "20") (pinfunction "VCC_20") (pintype "passive"))
      (node (ref "V15") (pin "3") (pinfunction "K_3") (pintype "passive"))
    )
    (net (code "117") (name "Net-(IC5-~{RESET})") (class "Default")
      (node (ref "IC5") (pin "19") (pinfunction "~{RESET}_19") (pintype "passive"))
      (node (ref "R22") (pin "2") (pintype "passive"))
      (node (ref "R23") (pin "2") (pintype "passive"))
    )
    (net (code "118") (name "Net-(IC6-Pad3)") (class "Default")
      (node (ref "IC6") (pin "3") (pintype "input"))
      (node (ref "R39") (pin "2") (pintype "passive"))
      (node (ref "X10") (pin "1") (pinfunction "1_1") (pintype "passive"))
    )
    (net (code "119") (name "Net-(IC6-Pad6)") (class "Default")
      (node (ref "IC6") (pin "6") (pintype "input"))
      (node (ref "R2") (pin "2") (pintype "passive"))
      (node (ref "R3") (pin "1") (pintype "passive"))
    )
    (net (code "120") (name "Net-(IC6-Pad7)") (class "Default")
      (node (ref "IC6") (pin "7") (pintype "output"))
      (node (ref "R2") (pin "1") (pintype "passive"))
      (node (ref "X10") (pin "4") (pinfunction "4_4") (pintype "passive"))
    )
    (net (code "121") (name "Net-(IC7-O0)") (class "Default")
      (node (ref "IC7") (pin "18") (pinfunction "O0_18") (pintype "passive"))
      (node (ref "L4") (pin "1") (pinfunction "1_1") (pintype "passive"))
    )
    (net (code "122") (name "Net-(IC7-O1)") (class "Default")
      (node (ref "IC7") (pin "17") (pinfunction "O1_17") (pintype "passive"))
      (node (ref "L5") (pin "1") (pinfunction "1_1") (pintype "passive"))
    )
    (net (code "123") (name "Net-(IC7-O2)") (class "Default")
      (node (ref "IC7") (pin "16") (pinfunction "O2_16") (pintype "passive"))
      (node (ref "L6") (pin "1") (pinfunction "1_1") (pintype "passive"))
    )
    (net (code "124") (name "Net-(IC7-O3)") (class "Default")
      (node (ref "IC7") (pin "15") (pinfunction "O3_15") (pintype "passive"))
      (node (ref "L7") (pin "1") (pinfunction "1_1") (pintype "passive"))
    )
    (net (code "125") (name "Net-(IC7-O4)") (class "Default")
      (node (ref "IC7") (pin "14") (pinfunction "O4_14") (pintype "passive"))
      (node (ref "L8") (pin "1") (pinfunction "1_1") (pintype "passive"))
    )
    (net (code "126") (name "Net-(IC7-O5)") (class "Default")
      (node (ref "IC7") (pin "13") (pinfunction "O5_13") (pintype "passive"))
      (node (ref "L9") (pin "1") (pinfunction "1_1") (pintype "passive"))
    )
    (net (code "127") (name "Net-(IC7-O6)") (class "Default")
      (node (ref "IC7") (pin "12") (pinfunction "O6_12") (pintype "passive"))
      (node (ref "L10") (pin "1") (pinfunction "1_1") (pintype "passive"))
    )
    (net (code "128") (name "Net-(IC7-O7)") (class "Default")
      (node (ref "IC7") (pin "11") (pinfunction "O7_11") (pintype "passive"))
      (node (ref "L11") (pin "1") (pinfunction "1_1") (pintype "passive"))
    )
    (net (code "129") (name "Net-(IC8-OSC_OUT)") (class "Default")
      (node (ref "IC8") (pin "13") (pinfunction "OSC_OUT_13") (pintype "output"))
      (node (ref "R52") (pin "2") (pintype "passive"))
    )
    (net (code "130") (name "Net-(IC8-PA3{slash}ADC123_IN3{slash})") (class "Default")
      (node (ref "IC8") (pin "26") (pinfunction "PA3/ADC123_IN3/_26") (pintype "bidirectional"))
      (node (ref "R42") (pin "2") (pintype "passive"))
      (node (ref "R43") (pin "2") (pintype "passive"))
      (node (ref "V9") (pin "2") (pinfunction "A2_2") (pintype "passive"))
    )
    (net (code "131") (name "Net-(IC8-PA5{slash}DAC_OUT2{slash}ADC12_IN5)") (class "Default")
      (node (ref "IC8") (pin "30") (pinfunction "PA5/DAC_OUT2/ADC12_IN5_30") (pintype "bidirectional"))
      (node (ref "TP1") (pin "1") (pinfunction "1_1") (pintype "passive"))
    )
    (net (code "132") (name "Net-(IC8-PB0{slash}ADC12_IN8{slash}TIM3_CH3)") (class "Default")
      (node (ref "IC8") (pin "35") (pinfunction "PB0/ADC12_IN8/TIM3_CH3_35") (pintype "bidirectional"))
      (node (ref "R44") (pin "1") (pintype "passive"))
      (node (ref "R45") (pin "1") (pintype "passive"))
      (node (ref "V10") (pin "1") (pinfunction "A1_1") (pintype "passive"))
      (node (ref "V10") (pin "2") (pinfunction "A2_2") (pintype "passive"))
    )
    (net (code "133") (name "Net-(IC8-PB1{slash}ADC12_IN9{slash}TIM3_CH4)") (class "Default")
      (node (ref "IC8") (pin "36") (pinfunction "PB1/ADC12_IN9/TIM3_CH4_36") (pintype "bidirectional"))
      (node (ref "R46") (pin "1") (pintype "passive"))
      (node (ref "R47") (pin "2") (pintype "passive"))
      (node (ref "V9") (pin "1") (pinfunction "A1_1") (pintype "passive"))
    )
    (net (code "134") (name "Net-(IC8-PC14)") (class "Default")
      (node (ref "C57") (pin "1") (pintype "passive"))
      (node (ref "G2") (pin "1") (pintype "passive"))
      (node (ref "IC8") (pin "8") (pinfunction "PC14_8") (pintype "bidirectional"))
    )
    (net (code "135") (name "Net-(IC8-PC15)") (class "Default")
      (node (ref "C58") (pin "1") (pintype "passive"))
      (node (ref "G2") (pin "2") (pintype "passive"))
      (node (ref "IC8") (pin "9") (pinfunction "PC15_9") (pintype "bidirectional"))
    )
    (net (code "136") (name "Net-(IC8-PD9)") (class "Default")
      (node (ref "IC8") (pin "56") (pinfunction "PD9_56") (pintype "bidirectional"))
      (node (ref "R36") (pin "2") (pintype "passive"))
    )
    (net (code "137") (name "Net-(IC8-PD10)") (class "Default")
      (node (ref "IC8") (pin "57") (pinfunction "PD10_57") (pintype "bidirectional"))
      (node (ref "R37") (pin "2") (pintype "passive"))
    )
    (net (code "138") (name "Net-(IC8-PD11)") (class "Default")
      (node (ref "IC8") (pin "58") (pinfunction "PD11_58") (pintype "bidirectional"))
      (node (ref "R38") (pin "2") (pintype "passive"))
    )
    (net (code "139") (name "Net-(IC8-PE0)") (class "Default")
      (node (ref "IC2") (pin "14") (pinfunction "C_14") (pintype "passive"))
      (node (ref "IC8") (pin "97") (pinfunction "PE0_97") (pintype "bidirectional"))
    )
    (net (code "140") (name "Net-(IC8-PE1)") (class "Default")
      (node (ref "IC2") (pin "16") (pinfunction "C_16") (pintype "passive"))
      (node (ref "IC8") (pin "98") (pinfunction "PE1_98") (pintype "bidirectional"))
    )
    (net (code "141") (name "Net-(IC8-PE2)") (class "Default")
      (node (ref "IC2") (pin "12") (pinfunction "C_12") (pintype "passive"))
      (node (ref "IC8") (pin "1") (pinfunction "PE2_1") (pintype "bidirectional"))
    )
    (net (code "142") (name "Net-(IC8-PE3)") (class "Default")
      (node (ref "IC2") (pin "10") (pinfunction "C_10") (pintype "passive"))
      (node (ref "IC8") (pin "2") (pinfunction "PE3_2") (pintype "bidirectional"))
    )
    (net (code "143") (name "Net-(IC8-Vbat)") (class "Default")
      (node (ref "C37") (pin "1") (pintype "passive"))
      (node (ref "IC8") (pin "6") (pinfunction "Vbat_6") (pintype "power_in"))
      (node (ref "V12") (pin "3") (pinfunction "K_3") (pintype "passive"))
    )
    (net (code "144") (name "Net-(IC8-Vcap_1)") (class "Default")
      (node (ref "C32") (pin "1") (pintype "passive"))
      (node (ref "IC8") (pin "49") (pinfunction "Vcap_1_49") (pintype "power_in"))
    )
    (net (code "145") (name "Net-(IC8-Vcap_2)") (class "Default")
      (node (ref "C33") (pin "1") (pintype "passive"))
      (node (ref "IC8") (pin "73") (pinfunction "Vcap_2_73") (pintype "power_in"))
    )
    (net (code "146") (name "Net-(IC9-IN)") (class "Default")
      (node (ref "C43") (pin "1") (pintype "passive"))
      (node (ref "IC9") (pin "1") (pinfunction "IN_1") (pintype "power_in"))
      (node (ref "L19") (pin "1") (pinfunction "1_1") (pintype "passive"))
    )
    (net (code "147") (name "Net-(IC10-C1+)") (class "Default")
      (node (ref "C5") (pin "1") (pintype "passive"))
      (node (ref "IC10") (pin "1") (pinfunction "C1+_1") (pintype "passive"))
    )
    (net (code "148") (name "Net-(IC10-C1-)") (class "Default")
      (node (ref "C5") (pin "2") (pintype "passive"))
      (node (ref "IC10") (pin "3") (pinfunction "C1-_3") (pintype "passive"))
    )
    (net (code "149") (name "Net-(IC10-C2+)") (class "Default")
      (node (ref "C6") (pin "2") (pintype "passive"))
      (node (ref "IC10") (pin "4") (pinfunction "C2+_4") (pintype "passive"))
    )
    (net (code "150") (name "Net-(IC10-C2-)") (class "Default")
      (node (ref "C6") (pin "1") (pintype "passive"))
      (node (ref "IC10") (pin "5") (pinfunction "C2-_5") (pintype "passive"))
    )
    (net (code "151") (name "Net-(IC10-VS+)") (class "Default")
      (node (ref "C7") (pin "2") (pintype "passive"))
      (node (ref "IC10") (pin "2") (pinfunction "VS+_2") (pintype "power_in"))
    )
    (net (code "152") (name "Net-(IC10-VS-)") (class "Default")
      (node (ref "C8") (pin "2") (pintype "passive"))
      (node (ref "IC10") (pin "6") (pinfunction "VS-_6") (pintype "power_in"))
    )
    (net (code "153") (name "Net-(IC11-IN)") (class "Default")
      (node (ref "C12") (pin "1") (pintype "passive"))
      (node (ref "IC11") (pin "3") (pinfunction "~{SD}_3") (pintype "passive"))
      (node (ref "IC11") (pin "5") (pinfunction "IN_5") (pintype "input"))
      (node (ref "R64") (pin "1") (pintype "passive"))
    )
    (net (code "154") (name "Net-(IC11-NR)") (class "Default")
      (node (ref "C13") (pin "2") (pintype "passive"))
      (node (ref "IC11") (pin "2") (pinfunction "NR_2") (pintype "power_in"))
    )
    (net (code "155") (name "Net-(JMP1-Pad2)") (class "Default")
      (node (ref "JMP1") (pin "2") (pintype "passive"))
      (node (ref "X20") (pin "2") (pinfunction "2_2") (pintype "passive"))
      (node (ref "X5") (pin "2") (pinfunction "2_2") (pintype "passive"))
    )
    (net (code "156") (name "Net-(L1-Pad2)") (class "Default")
      (node (ref "L1") (pin "2") (pinfunction "2_2") (pintype "passive"))
      (node (ref "X15") (pin "10") (pinfunction "10_10") (pintype "passive"))
    )
    (net (code "157") (name "Net-(L2-Pad2)") (class "Default")
      (node (ref "L2") (pin "2") (pinfunction "2_2") (pintype "passive"))
      (node (ref "X16") (pin "2") (pinfunction "2_2") (pintype "passive"))
    )
    (net (code "158") (name "Net-(L4-Pad2)") (class "Default")
      (node (ref "L4") (pin "2") (pinfunction "2_2") (pintype "passive"))
      (node (ref "X11") (pin "1") (pinfunction "1_1") (pintype "passive"))
    )
    (net (code "159") (name "Net-(L5-Pad2)") (class "Default")
      (node (ref "L5") (pin "2") (pinfunction "2_2") (pintype "passive"))
      (node (ref "X11") (pin "3") (pinfunction "3_3") (pintype "passive"))
    )
    (net (code "160") (name "Net-(L6-Pad2)") (class "Default")
      (node (ref "L6") (pin "2") (pinfunction "2_2") (pintype "passive"))
      (node (ref "X11") (pin "5") (pinfunction "5_5") (pintype "passive"))
    )
    (net (code "161") (name "Net-(L7-Pad2)") (class "Default")
      (node (ref "L7") (pin "2") (pinfunction "2_2") (pintype "passive"))
      (node (ref "X11") (pin "7") (pinfunction "7_7") (pintype "passive"))
    )
    (net (code "162") (name "Net-(L8-Pad2)") (class "Default")
      (node (ref "L8") (pin "2") (pinfunction "2_2") (pintype "passive"))
      (node (ref "X12") (pin "5") (pinfunction "5_5") (pintype "passive"))
    )
    (net (code "163") (name "Net-(L9-Pad2)") (class "Default")
      (node (ref "L9") (pin "2") (pinfunction "2_2") (pintype "passive"))
      (node (ref "X12") (pin "3") (pinfunction "3_3") (pintype "passive"))
    )
    (net (code "164") (name "Net-(L10-Pad2)") (class "Default")
      (node (ref "L10") (pin "2") (pinfunction "2_2") (pintype "passive"))
      (node (ref "X12") (pin "1") (pinfunction "1_1") (pintype "passive"))
    )
    (net (code "165") (name "Net-(L11-Pad2)") (class "Default")
      (node (ref "L11") (pin "2") (pinfunction "2_2") (pintype "passive"))
      (node (ref "X18") (pin "2") (pinfunction "2_2") (pintype "passive"))
    )
    (net (code "166") (name "Net-(L12-Pad2)") (class "Default")
      (node (ref "L12") (pin "2") (pinfunction "2_2") (pintype "passive"))
      (node (ref "X14") (pin "2") (pinfunction "2_2") (pintype "passive"))
    )
    (net (code "167") (name "Net-(L13-Pad2)") (class "Default")
      (node (ref "L13") (pin "2") (pinfunction "2_2") (pintype "passive"))
      (node (ref "X16") (pin "5") (pinfunction "5_5") (pintype "passive"))
    )
    (net (code "168") (name "Net-(L14-Pad2)") (class "Default")
      (node (ref "L14") (pin "2") (pinfunction "2_2") (pintype "passive"))
      (node (ref "X16") (pin "8") (pinfunction "8_8") (pintype "passive"))
    )
    (net (code "169") (name "Net-(L15-Pad2)") (class "Default")
      (node (ref "L15") (pin "2") (pinfunction "2_2") (pintype "passive"))
      (node (ref "X16") (pin "9") (pinfunction "9_9") (pintype "passive"))
    )
    (net (code "170") (name "Net-(L16-Pad2)") (class "Default")
      (node (ref "L16") (pin "2") (pinfunction "2_2") (pintype "passive"))
      (node (ref "X14") (pin "1") (pinfunction "1_1") (pintype "passive"))
    )
    (net (code "171") (name "Net-(L17-Pad2)") (class "Default")
      (node (ref "L17") (pin "2") (pinfunction "2_2") (pintype "passive"))
      (node (ref "X20") (pin "3") (pinfunction "3_3") (pintype "passive"))
    )
    (net (code "172") (name "Net-(L18-Pad2)") (class "Default")
      (node (ref "L18") (pin "2") (pinfunction "2_2") (pintype "passive"))
      (node (ref "X22") (pin "2") (pinfunction "2_2") (pintype "passive"))
    )
    (net (code "173") (name "Net-(L20-Pad2)") (class "Default")
      (node (ref "L20") (pin "2") (pinfunction "2_2") (pintype "passive"))
      (node (ref "X5") (pin "3") (pinfunction "3_3") (pintype "passive"))
    )
    (net (code "174") (name "Net-(L21-Pad2)") (class "Default")
      (node (ref "L21") (pin "2") (pinfunction "2_2") (pintype "passive"))
      (node (ref "X15") (pin "9") (pinfunction "9_9") (pintype "passive"))
    )
    (net (code "175") (name "Net-(L22-Pad2)") (class "Default")
      (node (ref "L22") (pin "2") (pinfunction "2_2") (pintype "passive"))
      (node (ref "X20") (pin "4") (pinfunction "4_4") (pintype "passive"))
      (node (ref "X5") (pin "4") (pinfunction "4_4") (pintype "passive"))
    )
    (net (code "176") (name "Net-(R5-Pad2)") (class "Default")
      (node (ref "R5") (pin "2") (pintype "passive"))
      (node (ref "V2") (pin "B") (pintype "passive"))
    )
    (net (code "177") (name "Net-(R7-Pad1)") (class "Default")
      (node (ref "R7") (pin "1") (pintype "passive"))
      (node (ref "V5") (pin "K") (pintype "passive"))
    )
    (net (code "178") (name "Net-(R8-Pad1)") (class "Default")
      (node (ref "R8") (pin "1") (pintype "passive"))
      (node (ref "X15") (pin "6") (pinfunction "6_6") (pintype "passive"))
    )
    (net (code "179") (name "Net-(R10-Pad1)") (class "Default")
      (node (ref "R10") (pin "1") (pintype "passive"))
      (node (ref "X15") (pin "4") (pinfunction "4_4") (pintype "passive"))
    )
    (net (code "180") (name "Net-(R11-Pad1)") (class "Default")
      (node (ref "R11") (pin "1") (pintype "passive"))
      (node (ref "X15") (pin "3") (pinfunction "3_3") (pintype "passive"))
    )
    (net (code "181") (name "Net-(R14-Pad1)") (class "Default")
      (node (ref "R14") (pin "1") (pintype "passive"))
      (node (ref "V6") (pin "B") (pinfunction "B_B") (pintype "passive"))
    )
    (net (code "182") (name "Net-(R16-Pad1)") (class "Default")
      (node (ref "R16") (pin "1") (pintype "passive"))
      (node (ref "V14") (pin "B") (pinfunction "B_B") (pintype "passive"))
    )
    (net (code "183") (name "Net-(R20-Pad2)") (class "Default")
      (node (ref "R20") (pin "2") (pintype "passive"))
      (node (ref "V7") (pin "1") (pinfunction "1_1") (pintype "passive"))
      (node (ref "X9") (pin "2") (pinfunction "2_2") (pintype "passive"))
    )
    (net (code "184") (name "Net-(R21-Pad2)") (class "Default")
      (node (ref "R21") (pin "2") (pintype "passive"))
      (node (ref "V7") (pin "5") (pinfunction "5_5") (pintype "passive"))
      (node (ref "X9") (pin "3") (pinfunction "3_3") (pintype "passive"))
    )
    (net (code "185") (name "Net-(R35-Pad1)") (class "Default")
      (node (ref "R35") (pin "1") (pintype "passive"))
      (node (ref "X10") (pin "3") (pinfunction "3_3") (pintype "passive"))
    )
    (net (code "186") (name "Net-(R35-Pad2)") (class "Default")
      (node (ref "R35") (pin "2") (pintype "passive"))
      (node (ref "V8") (pin "B") (pintype "passive"))
    )
    (net (code "187") (name "Net-(V15-A2)") (class "Default")
      (node (ref "JP1") (pin "1") (pintype "passive"))
      (node (ref "L3") (pin "2") (pinfunction "2_2") (pintype "passive"))
      (node (ref "V15") (pin "2") (pinfunction "A2_2") (pintype "passive"))
    )
    (net (code "188") (name "Pgnd") (class "Default")
      (node (ref "A1") (pin "3") (pinfunction "GND_3") (pintype "passive"))
      (node (ref "A2") (pin "3") (pinfunction "GND_3") (pintype "passive"))
      (node (ref "C1") (pin "2") (pintype "passive"))
      (node (ref "C2") (pin "1") (pintype "passive"))
      (node (ref "C25") (pin "2") (pintype "passive"))
      (node (ref "C29") (pin "2") (pintype "passive"))
      (node (ref "H12") (pin "K") (pintype "passive"))
      (node (ref "IC7") (pin "9") (pinfunction "GND_9") (pintype "passive"))
      (node (ref "J1") (pin "2") (pintype "passive"))
      (node (ref "J2") (pin "1") (pintype "passive"))
      (node (ref "R1") (pin "2") (pintype "passive"))
      (node (ref "R39") (pin "1") (pintype "passive"))
      (node (ref "R40") (pin "1") (pintype "passive"))
      (node (ref "R63") (pin "2") (pintype "passive"))
      (node (ref "V1") (pin "2") (pinfunction "2_2") (pintype "passive"))
      (node (ref "V2") (pin "E") (pintype "passive"))
      (node (ref "V8") (pin "E") (pintype "passive"))
      (node (ref "X1") (pin "2") (pinfunction "2_2") (pintype "passive"))
      (node (ref "X1") (pin "4") (pinfunction "4_4") (pintype "passive"))
      (node (ref "X15") (pin "2") (pinfunction "2_2") (pintype "passive"))
      (node (ref "X2") (pin "2") (pinfunction "2_2") (pintype "passive"))
      (node (ref "X20") (pin "1") (pinfunction "1_1") (pintype "passive"))
      (node (ref "X5") (pin "1") (pinfunction "1_1") (pintype "passive"))
    )
    (net (code "189") (name "Shield") (class "Default")
      (node (ref "J1") (pin "1") (pintype "passive"))
      (node (ref "X16") (pin "10") (pinfunction "10_10") (pintype "passive"))
      (node (ref "X6") (pin "7") (pinfunction "7_7") (pintype "passive"))
      (node (ref "X7") (pin "7") (pinfunction "7_7") (pintype "passive"))
    )
    (net (code "190") (name "VCCIO") (class "Default")
      (node (ref "C23") (pin "2") (pintype "passive"))
      (node (ref "H10") (pin "A") (pinfunction "A_A") (pintype "passive"))
      (node (ref "H11") (pin "A") (pinfunction "A_A") (pintype "passive"))
      (node (ref "H9") (pin "A") (pinfunction "A_A") (pintype "passive"))
      (node (ref "IC5") (pin "17") (pinfunction "3V3OUT_17") (pintype "passive"))
      (node (ref "IC5") (pin "4") (pinfunction "VCCIO_4") (pintype "passive"))
    )
    (net (code "191") (name "Vref_3V3") (class "Default")
      (node (ref "C41") (pin "1") (pintype "passive"))
      (node (ref "C42") (pin "1") (pintype "passive"))
      (node (ref "IC8") (pin "21") (pinfunction "Vref+_21") (pintype "power_in"))
      (node (ref "IC8") (pin "22") (pinfunction "VddA_22") (pintype "power_in"))
      (node (ref "IC9") (pin "2") (pinfunction "OUT_2") (pintype "power_in"))
      (node (ref "R53") (pin "2") (pintype "passive"))
      (node (ref "R54") (pin "2") (pintype "passive"))
    )
    (net (code "192") (name "unconnected-(A2-ON{slash}OFF-Pad1)") (class "Default")
      (node (ref "A2") (pin "1") (pinfunction "ON/OFF_1") (pintype "passive"))
    )
    (net (code "193") (name "unconnected-(A2-TRIM-Pad4)") (class "Default")
      (node (ref "A2") (pin "4") (pinfunction "TRIM_4") (pintype "passive"))
    )
    (net (code "194") (name "unconnected-(B1-NC-Pad1)") (class "Default")
      (node (ref "B1") (pin "1") (pinfunction "NC_1") (pintype "passive"))
    )
    (net (code "195") (name "unconnected-(B1-NC-Pad5)") (class "Default")
      (node (ref "B1") (pin "5") (pinfunction "NC_5") (pintype "passive"))
    )
    (net (code "196") (name "unconnected-(B1-NC-Pad6)") (class "Default")
      (node (ref "B1") (pin "6") (pinfunction "NC_6") (pintype "passive"))
    )
    (net (code "197") (name "unconnected-(B1-NC-Pad7)") (class "Default")
      (node (ref "B1") (pin "7") (pinfunction "NC_7") (pintype "passive"))
    )
    (net (code "198") (name "unconnected-(B1-NC-Pad8)") (class "Default")
      (node (ref "B1") (pin "8") (pinfunction "NC_8") (pintype "passive"))
    )
    (net (code "199") (name "unconnected-(B2-NC-Pad1)") (class "Default")
      (node (ref "B2") (pin "1") (pinfunction "NC_1") (pintype "passive"))
    )
    (net (code "200") (name "unconnected-(B2-NC-Pad5)") (class "Default")
      (node (ref "B2") (pin "5") (pinfunction "NC_5") (pintype "passive"))
    )
    (net (code "201") (name "unconnected-(B2-NC-Pad6)") (class "Default")
      (node (ref "B2") (pin "6") (pinfunction "NC_6") (pintype "passive"))
    )
    (net (code "202") (name "unconnected-(B2-NC-Pad7)") (class "Default")
      (node (ref "B2") (pin "7") (pinfunction "NC_7") (pintype "passive"))
    )
    (net (code "203") (name "unconnected-(B2-NC-Pad8)") (class "Default")
      (node (ref "B2") (pin "8") (pinfunction "NC_8") (pintype "passive"))
    )
    (net (code "204") (name "unconnected-(B3-NC-Pad1)") (class "Default")
      (node (ref "B3") (pin "1") (pinfunction "NC_1") (pintype "passive"))
    )
    (net (code "205") (name "unconnected-(B3-NC-Pad5)") (class "Default")
      (node (ref "B3") (pin "5") (pinfunction "NC_5") (pintype "passive"))
    )
    (net (code "206") (name "unconnected-(B3-NC-Pad6)") (class "Default")
      (node (ref "B3") (pin "6") (pinfunction "NC_6") (pintype "passive"))
    )
    (net (code "207") (name "unconnected-(B3-NC-Pad7)") (class "Default")
      (node (ref "B3") (pin "7") (pinfunction "NC_7") (pintype "passive"))
    )
    (net (code "208") (name "unconnected-(B3-NC-Pad8)") (class "Default")
      (node (ref "B3") (pin "8") (pinfunction "NC_8") (pintype "passive"))
    )
    (net (code "209") (name "unconnected-(B4-NC-Pad1)") (class "Default")
      (node (ref "B4") (pin "1") (pinfunction "NC_1") (pintype "passive"))
    )
    (net (code "210") (name "unconnected-(B4-NC-Pad5)") (class "Default")
      (node (ref "B4") (pin "5") (pinfunction "NC_5") (pintype "passive"))
    )
    (net (code "211") (name "unconnected-(B4-NC-Pad6)") (class "Default")
      (node (ref "B4") (pin "6") (pinfunction "NC_6") (pintype "passive"))
    )
    (net (code "212") (name "unconnected-(B4-NC-Pad7)") (class "Default")
      (node (ref "B4") (pin "7") (pinfunction "NC_7") (pintype "passive"))
    )
    (net (code "213") (name "unconnected-(B4-NC-Pad8)") (class "Default")
      (node (ref "B4") (pin "8") (pinfunction "NC_8") (pintype "passive"))
    )
    (net (code "214") (name "unconnected-(IC5-NC-Pad8)") (class "Default")
      (node (ref "IC5") (pin "8") (pinfunction "NC_8") (pintype "passive"))
    )
    (net (code "215") (name "unconnected-(IC5-NC-Pad24)") (class "Default")
      (node (ref "IC5") (pin "24") (pinfunction "NC_24") (pintype "passive"))
    )
    (net (code "216") (name "unconnected-(IC5-OSCI-Pad27)") (class "Default")
      (node (ref "IC5") (pin "27") (pinfunction "OSCI_27") (pintype "passive"))
    )
    (net (code "217") (name "unconnected-(IC5-OSCO-Pad28)") (class "Default")
      (node (ref "IC5") (pin "28") (pinfunction "OSCO_28") (pintype "passive"))
    )
    (net (code "218") (name "unconnected-(IC5-~{CTS}-Pad11)") (class "Default")
      (node (ref "IC5") (pin "11") (pinfunction "~{CTS}_11") (pintype "passive"))
    )
    (net (code "219") (name "unconnected-(IC5-~{DCD}-Pad10)") (class "Default")
      (node (ref "IC5") (pin "10") (pinfunction "~{DCD}_10") (pintype "passive"))
    )
    (net (code "220") (name "unconnected-(IC5-~{DSR}-Pad9)") (class "Default")
      (node (ref "IC5") (pin "9") (pinfunction "~{DSR}_9") (pintype "passive"))
    )
    (net (code "221") (name "unconnected-(IC5-~{DTR}-Pad2)") (class "Default")
      (node (ref "IC5") (pin "2") (pinfunction "~{DTR}_2") (pintype "passive"))
    )
    (net (code "222") (name "unconnected-(IC5-~{RI}-Pad6)") (class "Default")
      (node (ref "IC5") (pin "6") (pinfunction "~{RI}_6") (pintype "passive"))
    )
    (net (code "223") (name "unconnected-(IC5-~{RTS}-Pad3)") (class "Default")
      (node (ref "IC5") (pin "3") (pinfunction "~{RTS}_3") (pintype "passive"))
    )
    (net (code "224") (name "unconnected-(IC6B-VCC-Pad8)") (class "Default")
      (node (ref "IC6") (pin "8") (pinfunction "VCC_8") (pintype "power_in"))
    )
    (net (code "225") (name "unconnected-(IC6B-VEE-Pad4)") (class "Default")
      (node (ref "IC6") (pin "4") (pinfunction "VEE_4") (pintype "power_in"))
    )
    (net (code "226") (name "unconnected-(IC8-PA11{slash}USBDM-Pad70)") (class "Default")
      (node (ref "IC8") (pin "70") (pinfunction "PA11/USBDM_70") (pintype "bidirectional"))
    )
    (net (code "227") (name "unconnected-(IC8-PA12{slash}USBDP-Pad71)") (class "Default")
      (node (ref "IC8") (pin "71") (pinfunction "PA12/USBDP_71") (pintype "bidirectional"))
    )
    (net (code "228") (name "unconnected-(IC8-PA15{slash}TIM2_CH1-Pad77)") (class "Default")
      (node (ref "IC8") (pin "77") (pinfunction "PA15/TIM2_CH1_77") (pintype "bidirectional"))
    )
    (net (code "229") (name "unconnected-(IC8-PB7{slash}{slash}I2C1_SDA-Pad93)") (class "Default")
      (node (ref "IC8") (pin "93") (pinfunction "PB7//I2C1_SDA_93") (pintype "bidirectional"))
    )
    (net (code "230") (name "unconnected-(IC8-PB9{slash}TIM11_CH1-Pad96)") (class "Default")
      (node (ref "IC8") (pin "96") (pinfunction "PB9/TIM11_CH1_96") (pintype "bidirectional"))
    )
    (net (code "231") (name "unconnected-(IC8-PB10{slash}TIM2_CH3-Pad47)") (class "Default")
      (node (ref "IC8") (pin "47") (pinfunction "PB10/TIM2_CH3_47") (pintype "bidirectional"))
    )
    (net (code "232") (name "unconnected-(IC8-PB11{slash}TIM2_CH4{slash}USART3_RX-Pad48)") (class "Default")
      (node (ref "IC8") (pin "48") (pinfunction "PB11/TIM2_CH4/USART3_RX_48") (pintype "bidirectional"))
    )
    (net (code "233") (name "unconnected-(IC8-PB12-Pad51)") (class "Default")
      (node (ref "IC8") (pin "51") (pinfunction "PB12_51") (pintype "bidirectional"))
    )
    (net (code "234") (name "unconnected-(IC8-PC12-Pad80)") (class "Default")
      (node (ref "IC8") (pin "80") (pinfunction "PC12_80") (pintype "bidirectional"))
    )
    (net (code "235") (name "unconnected-(IC8-PC13-Pad7)") (class "Default")
      (node (ref "IC8") (pin "7") (pinfunction "PC13_7") (pintype "bidirectional"))
    )
    (net (code "236") (name "unconnected-(IC8-PD8-Pad55)") (class "Default")
      (node (ref "IC8") (pin "55") (pinfunction "PD8_55") (pintype "bidirectional"))
    )
    (net (code "237") (name "unconnected-(IC8-PD14{slash}TIM4_CH3-Pad61)") (class "Default")
      (node (ref "IC8") (pin "61") (pinfunction "PD14/TIM4_CH3_61") (pintype "bidirectional"))
    )
    (net (code "238") (name "unconnected-(IC8-PD15{slash}TIM4_CH4-Pad62)") (class "Default")
      (node (ref "IC8") (pin "62") (pinfunction "PD15/TIM4_CH4_62") (pintype "bidirectional"))
    )
    (net (code "239") (name "unconnected-(IC8-PE4-Pad3)") (class "Default")
      (node (ref "IC8") (pin "3") (pinfunction "PE4_3") (pintype "bidirectional"))
    )
    (net (code "240") (name "unconnected-(IC8-PE7-Pad38)") (class "Default")
      (node (ref "IC8") (pin "38") (pinfunction "PE7_38") (pintype "bidirectional"))
    )
    (net (code "241") (name "unconnected-(IC8-PE8-Pad39)") (class "Default")
      (node (ref "IC8") (pin "39") (pinfunction "PE8_39") (pintype "bidirectional"))
    )
    (net (code "242") (name "unconnected-(IC8-PE10-Pad41)") (class "Default")
      (node (ref "IC8") (pin "41") (pinfunction "PE10_41") (pintype "bidirectional"))
    )
    (net (code "243") (name "unconnected-(IC8-PE12-Pad43)") (class "Default")
      (node (ref "IC8") (pin "43") (pinfunction "PE12_43") (pintype "bidirectional"))
    )
    (net (code "244") (name "unconnected-(IC8-PE15-Pad46)") (class "Default")
      (node (ref "IC8") (pin "46") (pinfunction "PE15_46") (pintype "bidirectional"))
    )
    (net (code "245") (name "unconnected-(IC10-DIN2-Pad10)") (class "Default")
      (node (ref "IC10") (pin "10") (pinfunction "DIN2_10") (pintype "input"))
    )
    (net (code "246") (name "unconnected-(IC10-RIN2-Pad8)") (class "Default")
      (node (ref "IC10") (pin "8") (pinfunction "RIN2_8") (pintype "input"))
    )
    (net (code "247") (name "unconnected-(IC10-~{DOUT2}-Pad7)") (class "Default")
      (node (ref "IC10") (pin "7") (pinfunction "~{DOUT2}_7") (pintype "output"))
    )
    (net (code "248") (name "unconnected-(IC10-~{ROUT2}-Pad9)") (class "Default")
      (node (ref "IC10") (pin "9") (pinfunction "~{ROUT2}_9") (pintype "output"))
    )
    (net (code "249") (name "unconnected-(IC11-~{ERR}-Pad6)") (class "Default")
      (node (ref "IC11") (pin "6") (pinfunction "~{ERR}_6") (pintype "power_in"))
    )
    (net (code "250") (name "unconnected-(V1-Pad3)") (class "Default")
      (node (ref "V1") (pin "3") (pinfunction "3_3") (pintype "passive"))
    )
    (net (code "251") (name "unconnected-(V4-Pad4)") (class "Default")
      (node (ref "V4") (pin "4") (pinfunction "4_4") (pintype "passive"))
    )
    (net (code "252") (name "unconnected-(V7-Pad3)") (class "Default")
      (node (ref "V7") (pin "3") (pinfunction "3_3") (pintype "passive"))
    )
    (net (code "253") (name "unconnected-(V16-Pad5)") (class "Default")
      (node (ref "V16") (pin "5") (pinfunction "5_5") (pintype "passive"))
    )
    (net (code "254") (name "unconnected-(X8-Pad2)") (class "Default")
      (node (ref "X8") (pin "2") (pinfunction "2_2") (pintype "passive"))
    )
    (net (code "255") (name "unconnected-(X9-Pad4)") (class "Default")
      (node (ref "X9") (pin "4") (pinfunction "4_4") (pintype "passive"))
    )
    (net (code "256") (name "unconnected-(X10-Pad2)") (class "Default")
      (node (ref "X10") (pin "2") (pinfunction "2_2") (pintype "passive"))
    )
  )
)
